# freetserv.net
KiCad netlist of a schematic drawn in EAGLE
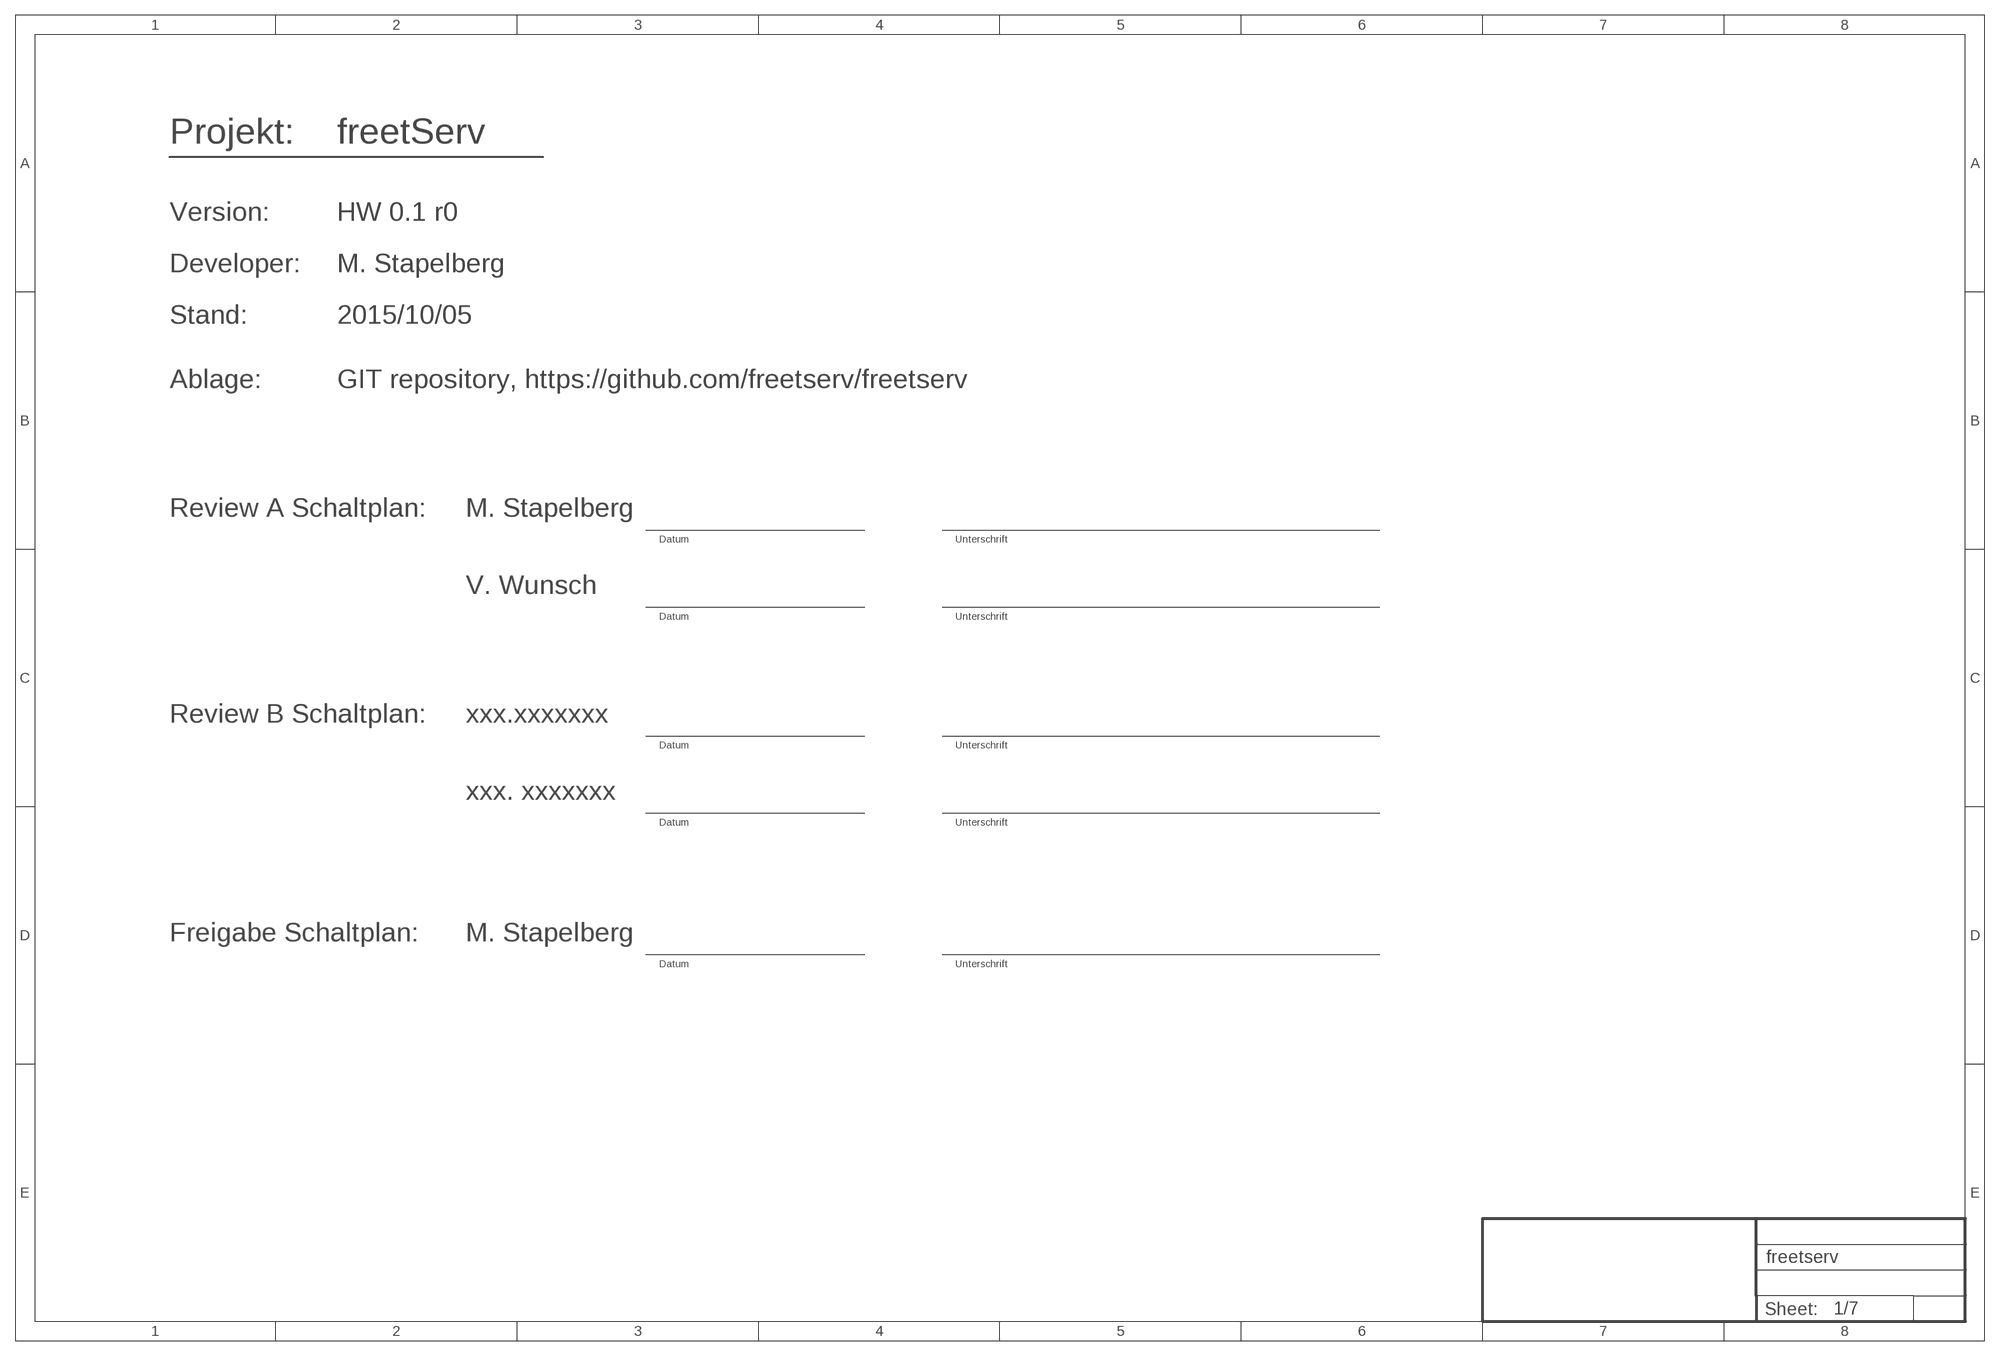
[diagram p0: schematic, sheet 1]
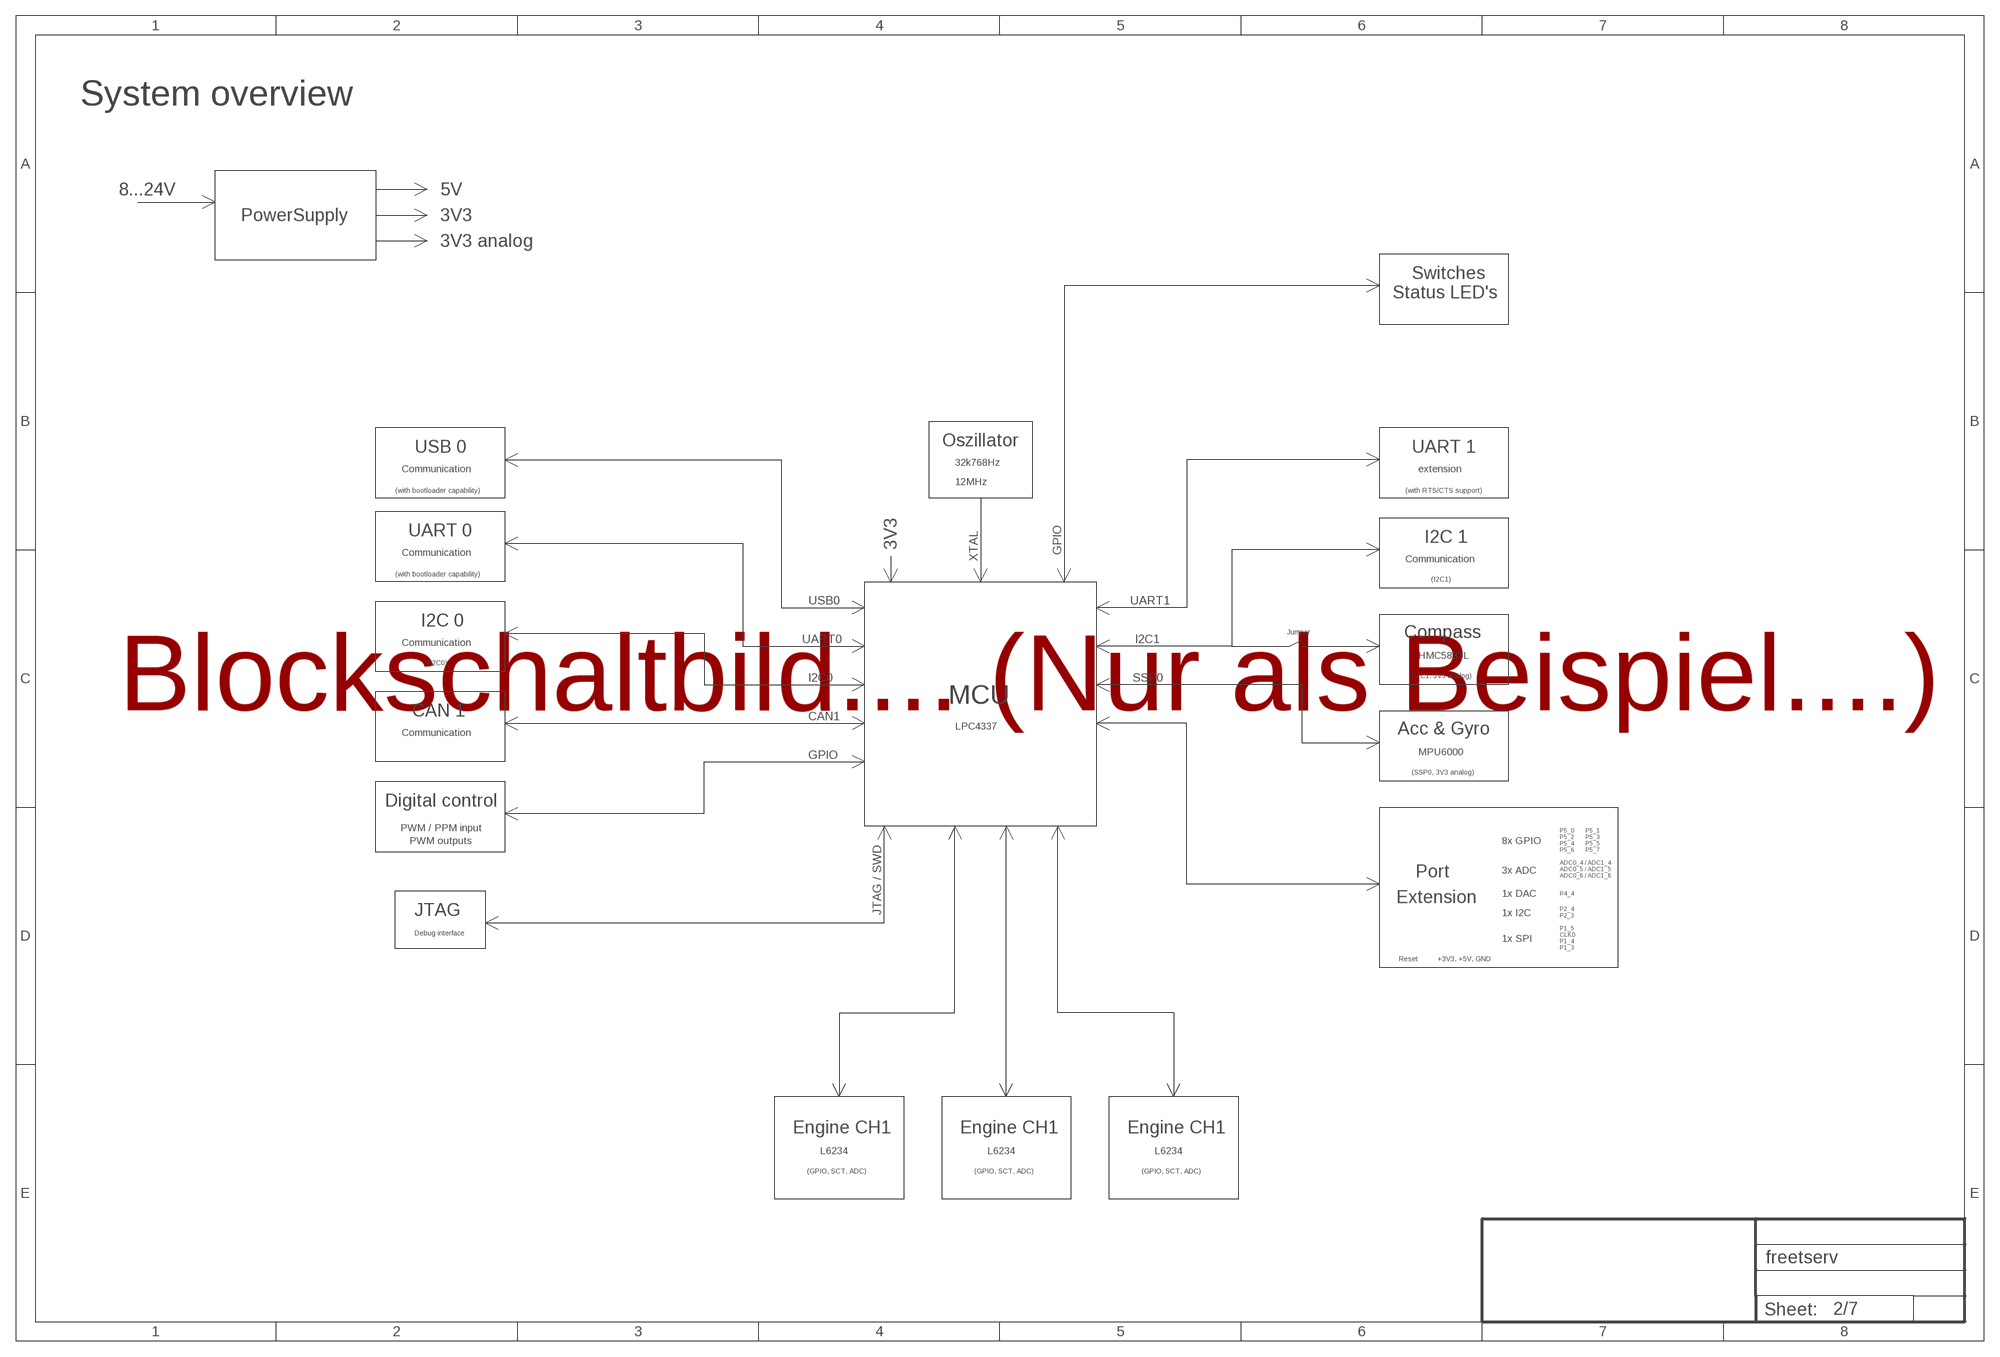
[diagram p1: schematic, sheet 2]
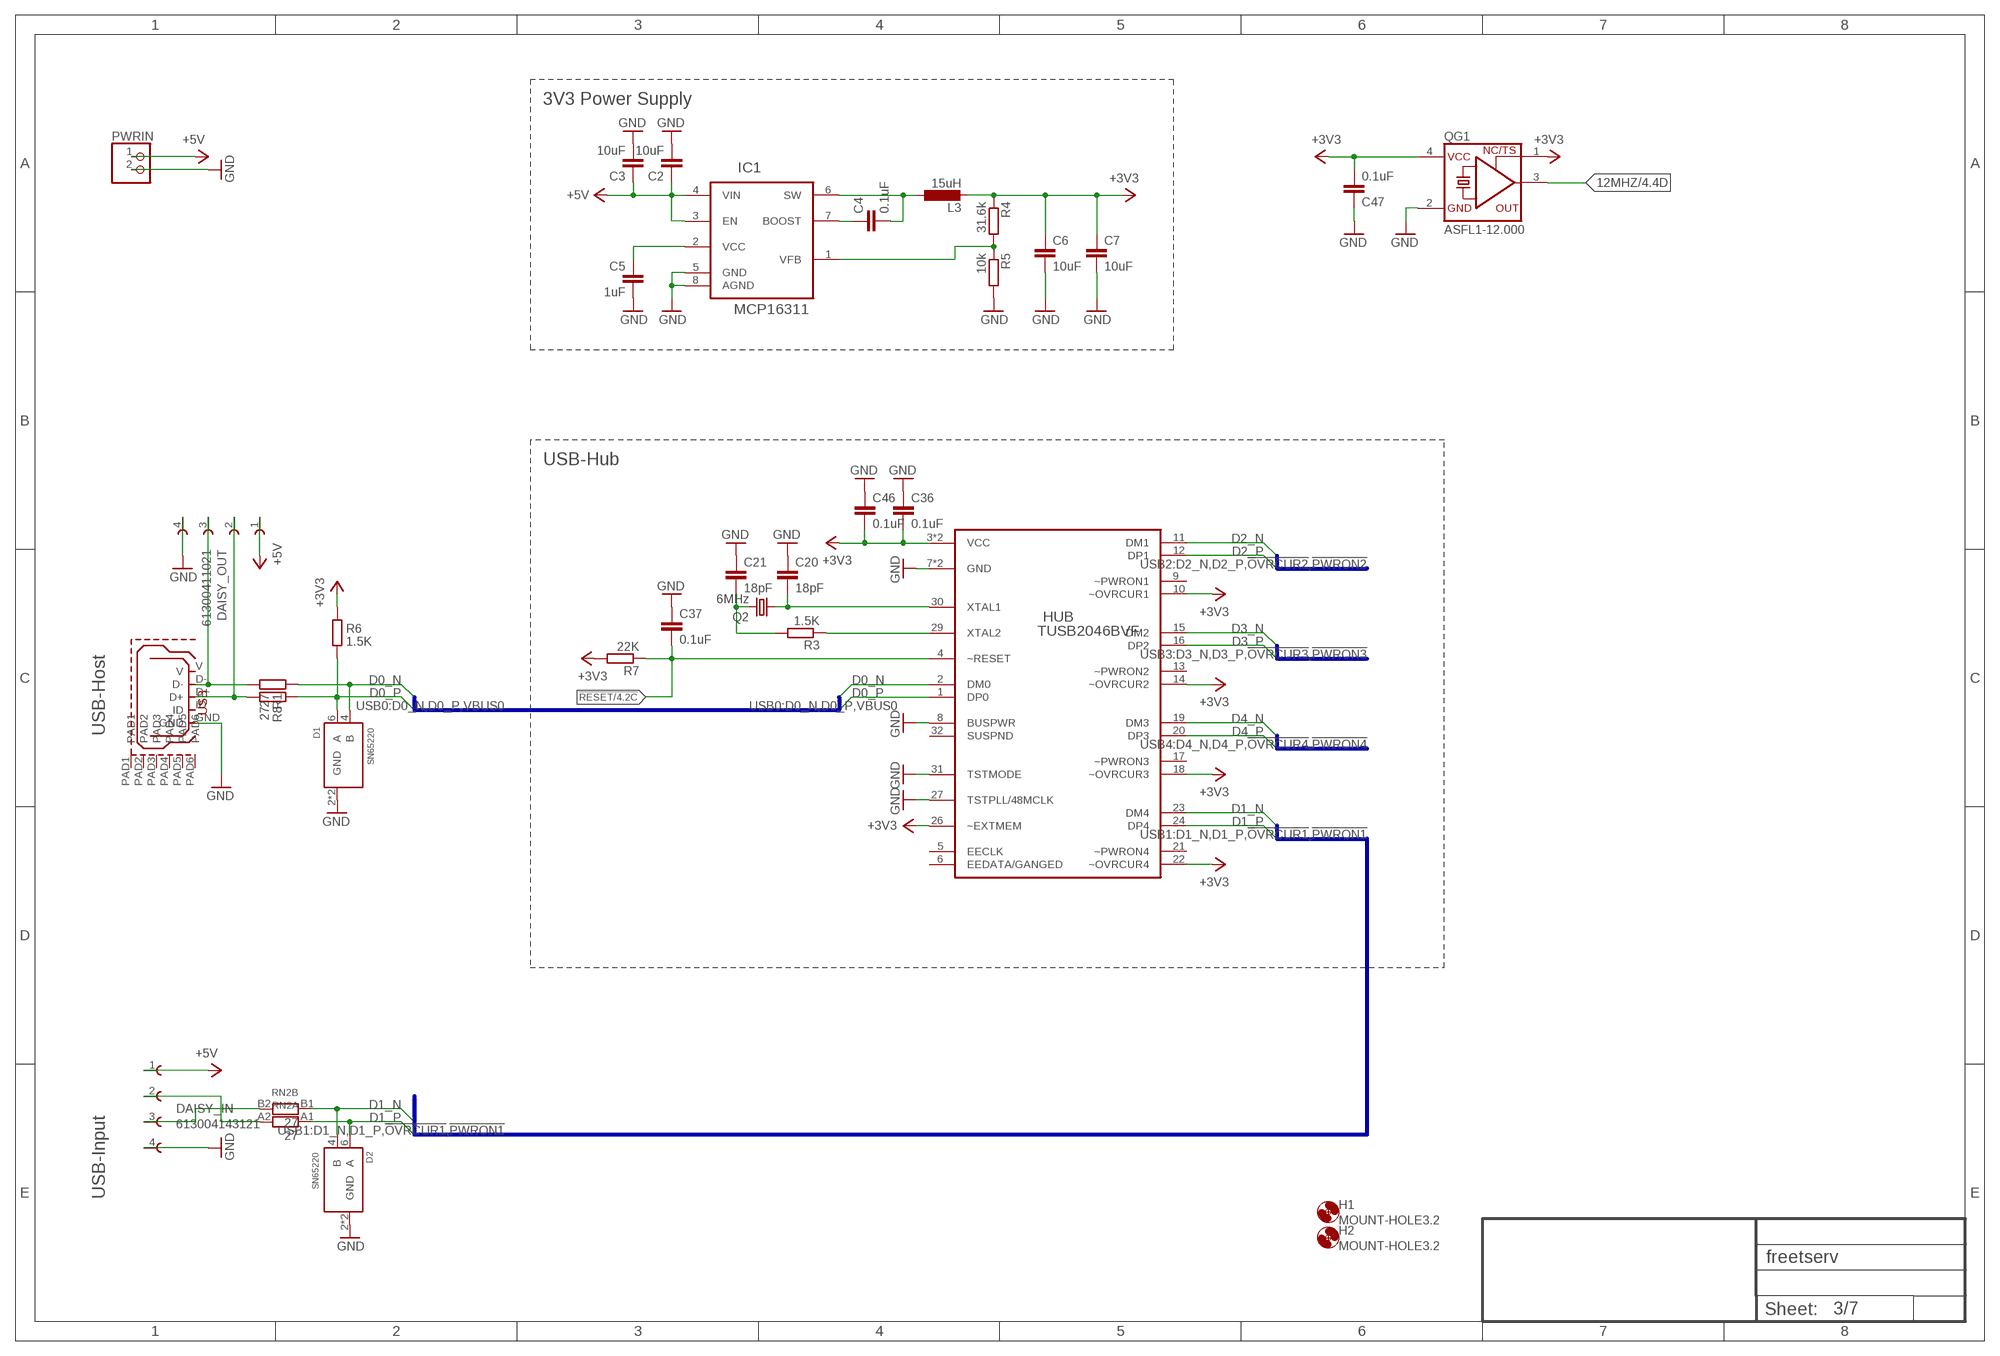
[diagram p2: schematic, sheet 3]
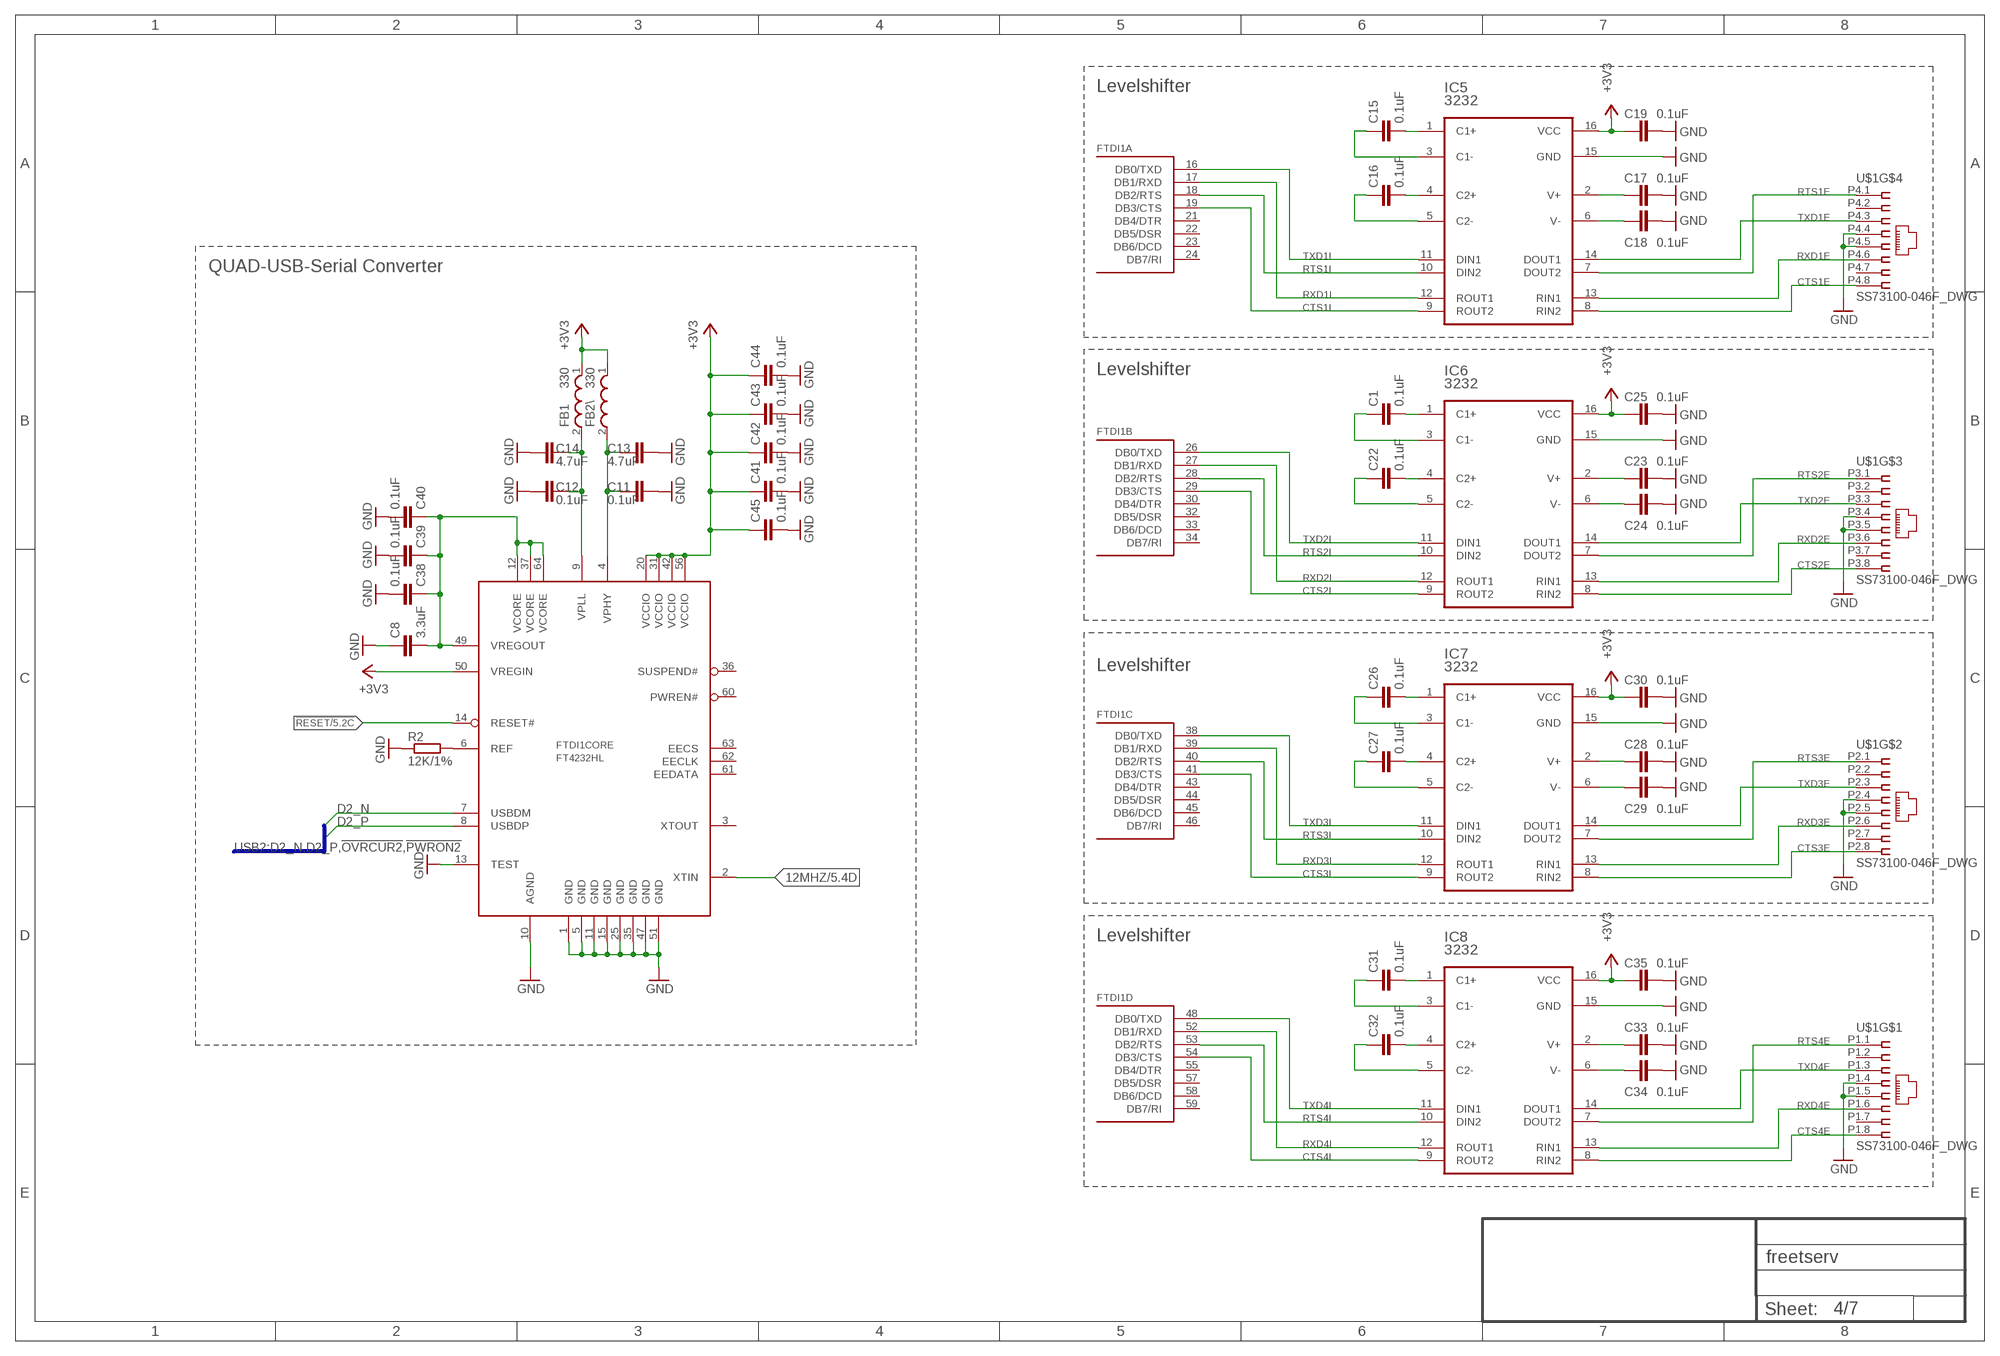
[diagram p3: schematic, sheet 4]
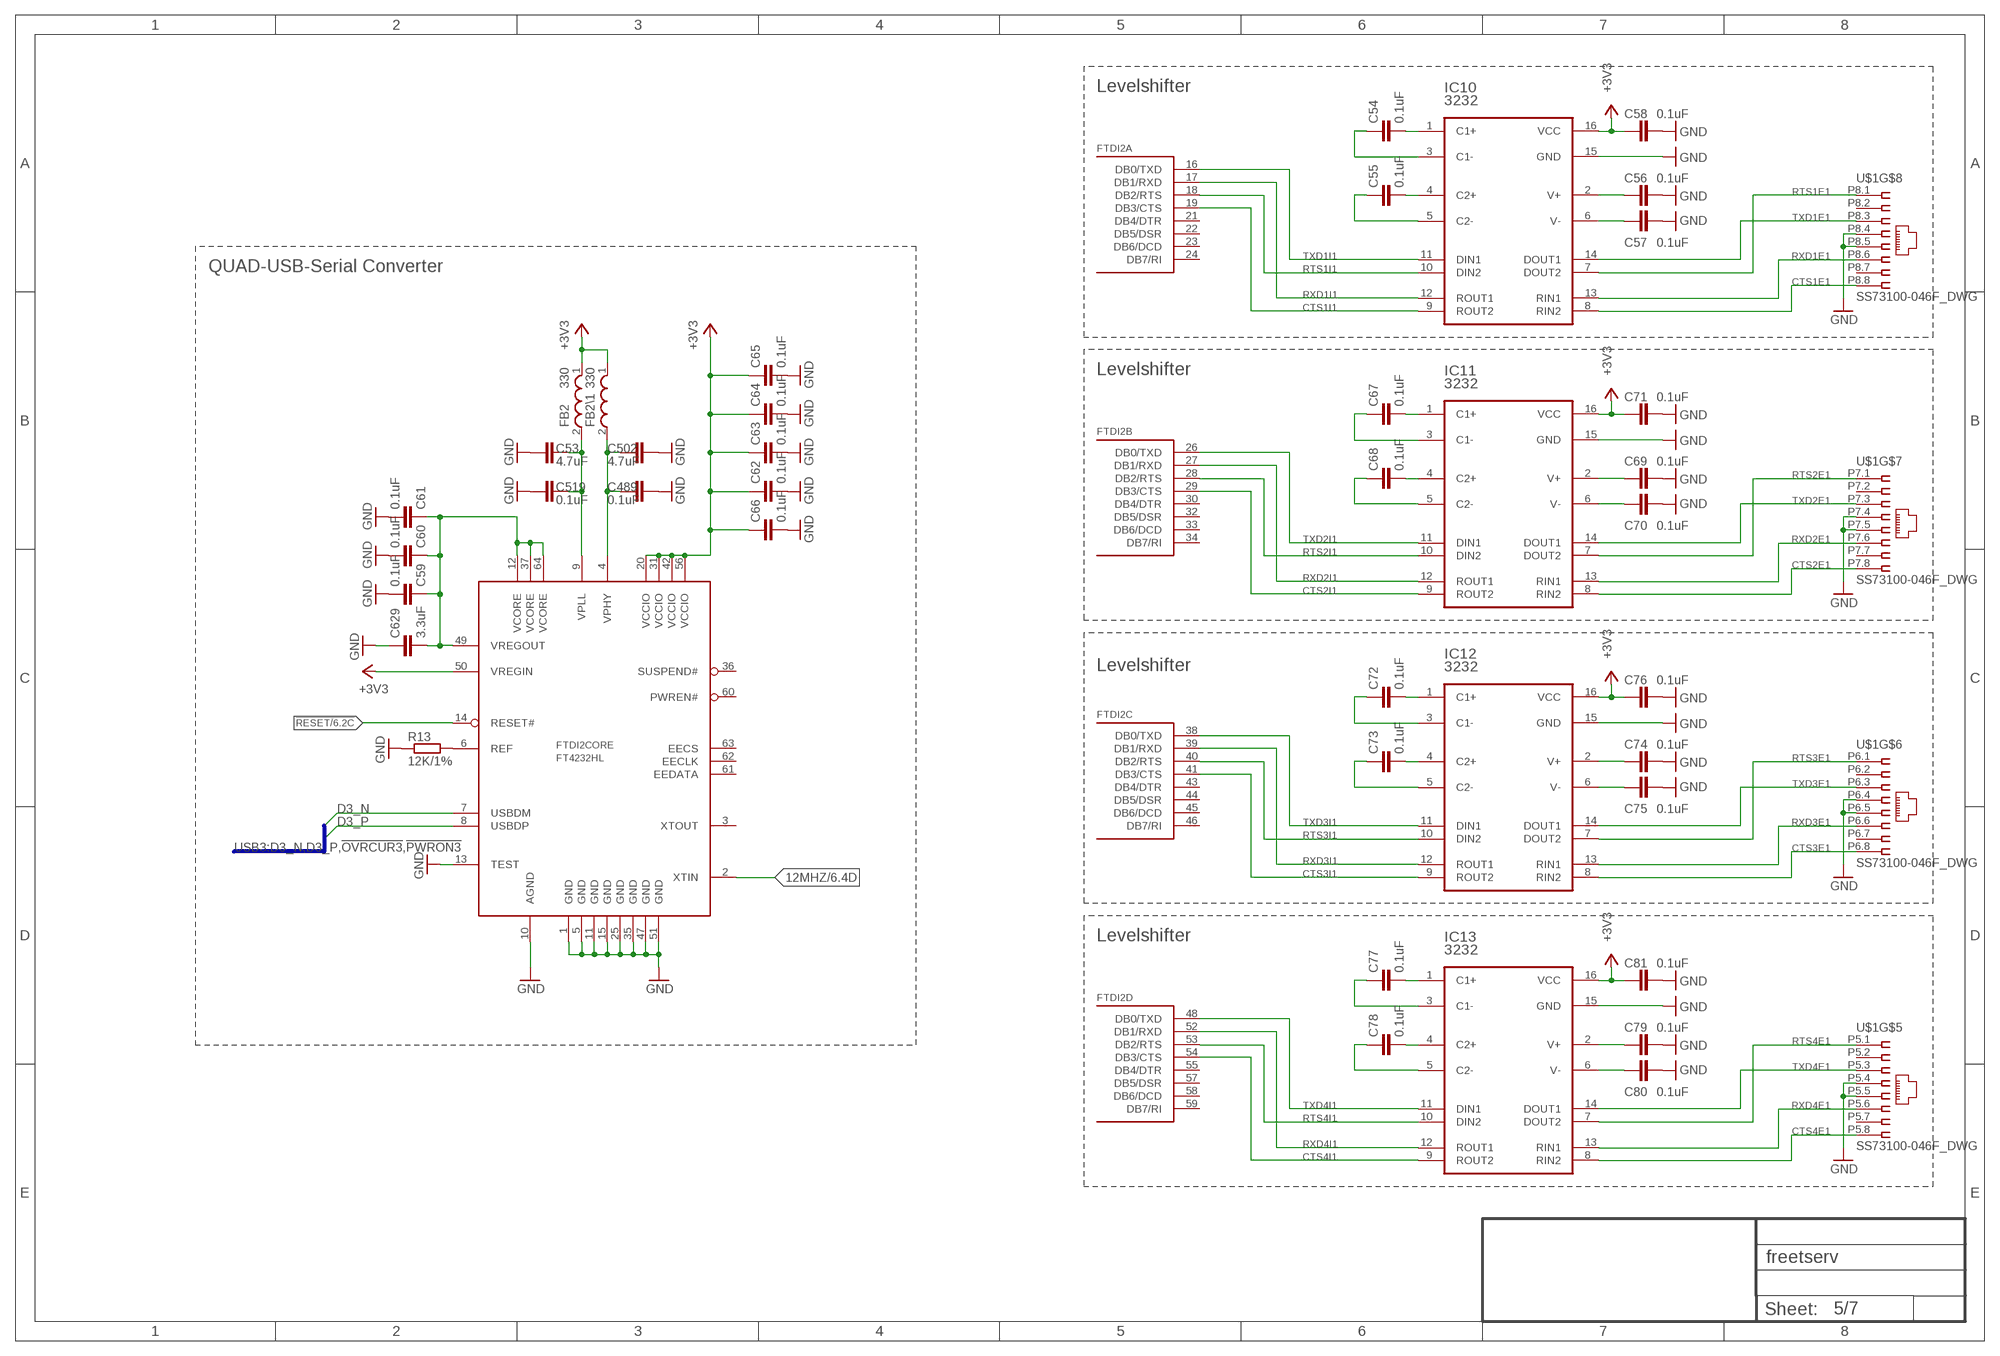
[diagram p4: schematic, sheet 5]
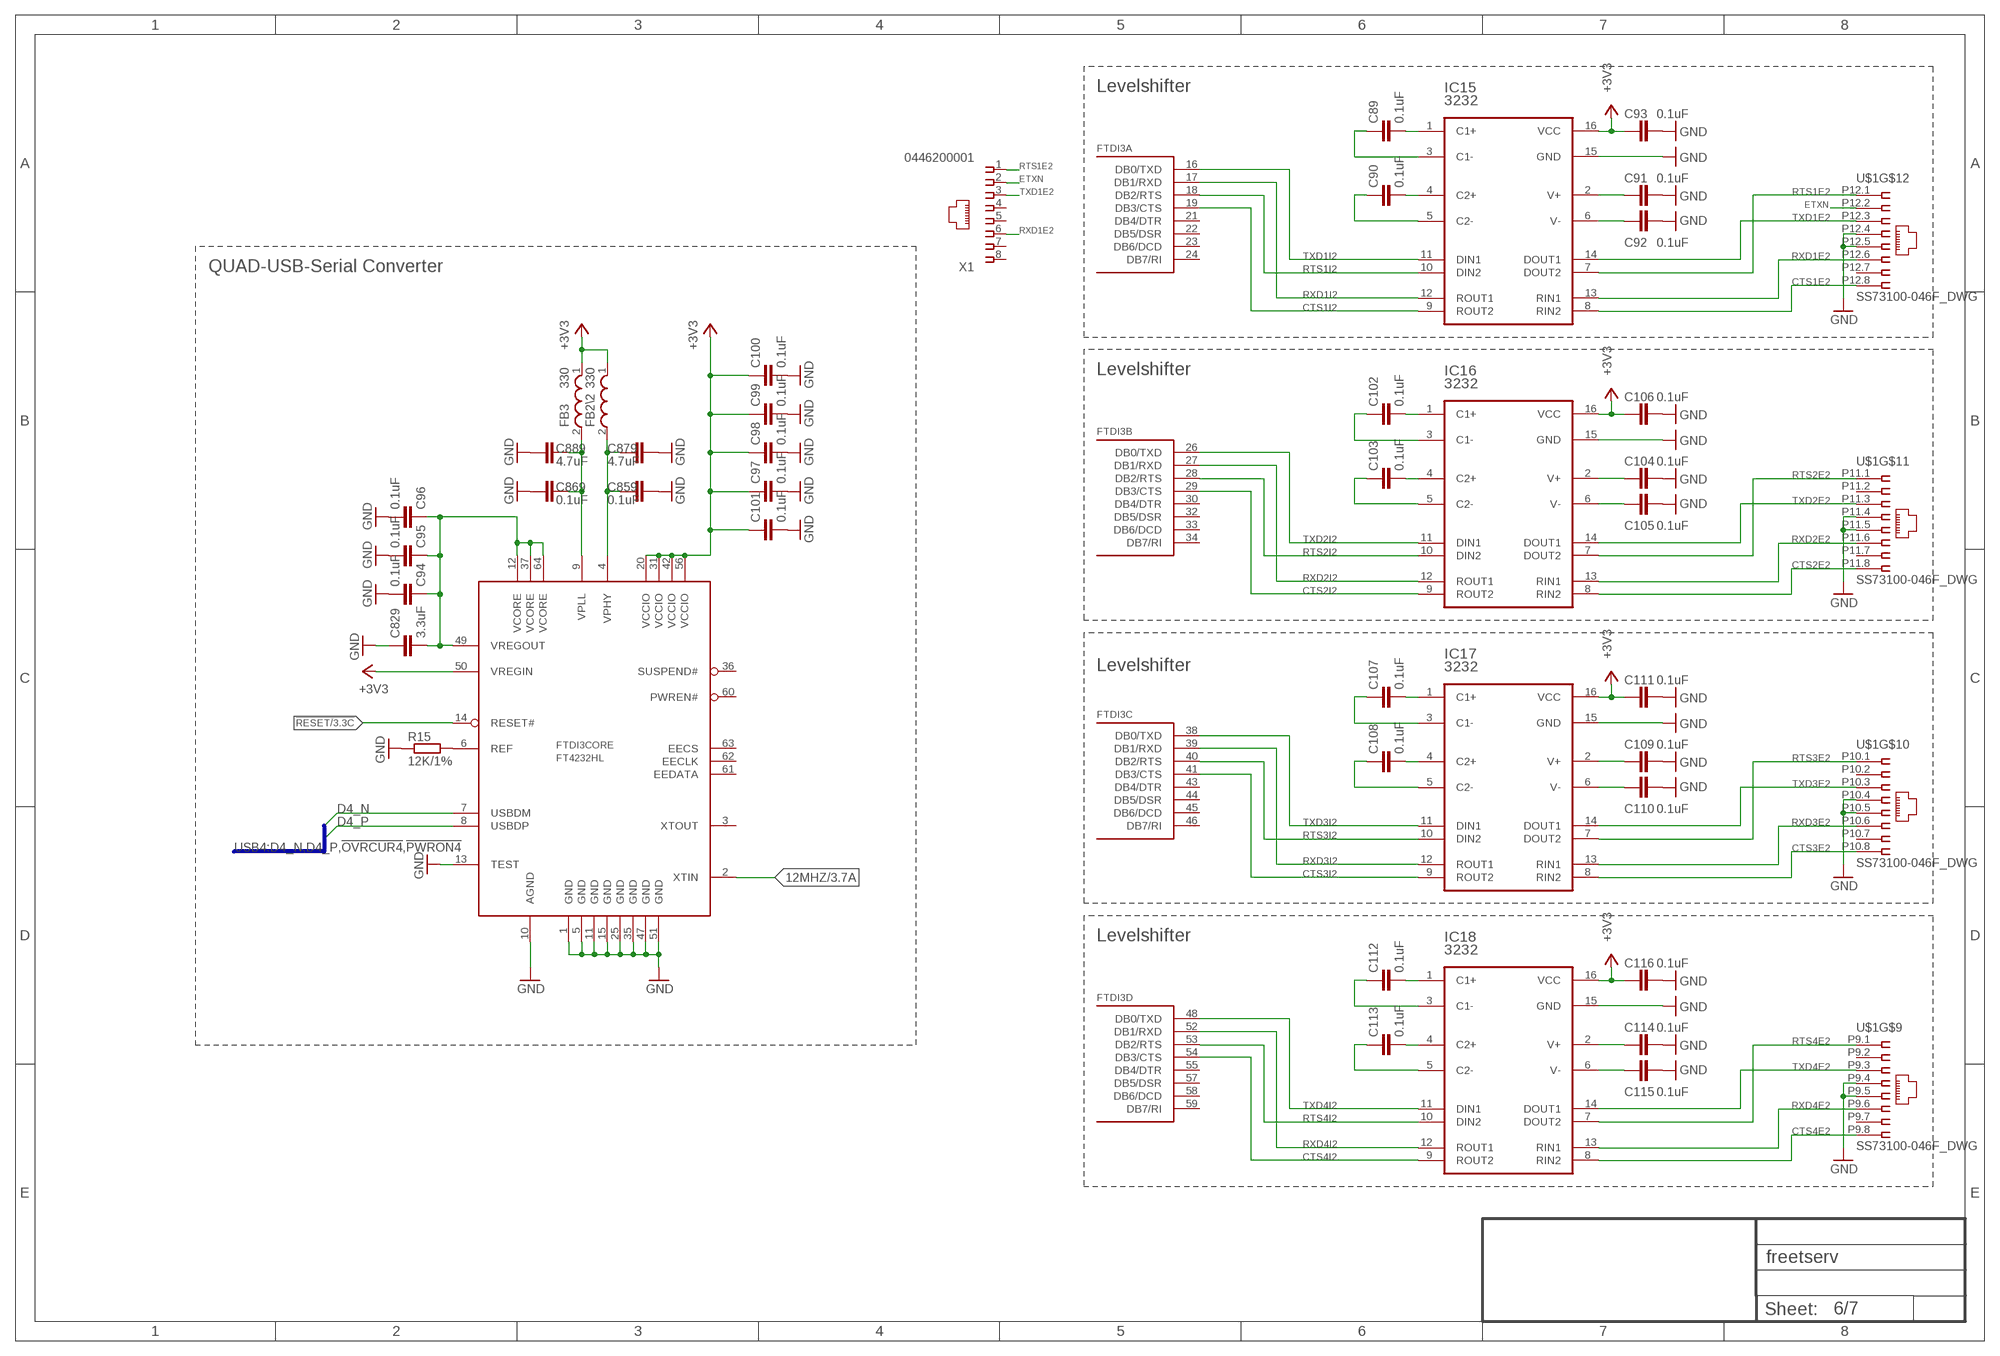
[diagram p5: schematic, sheet 6]
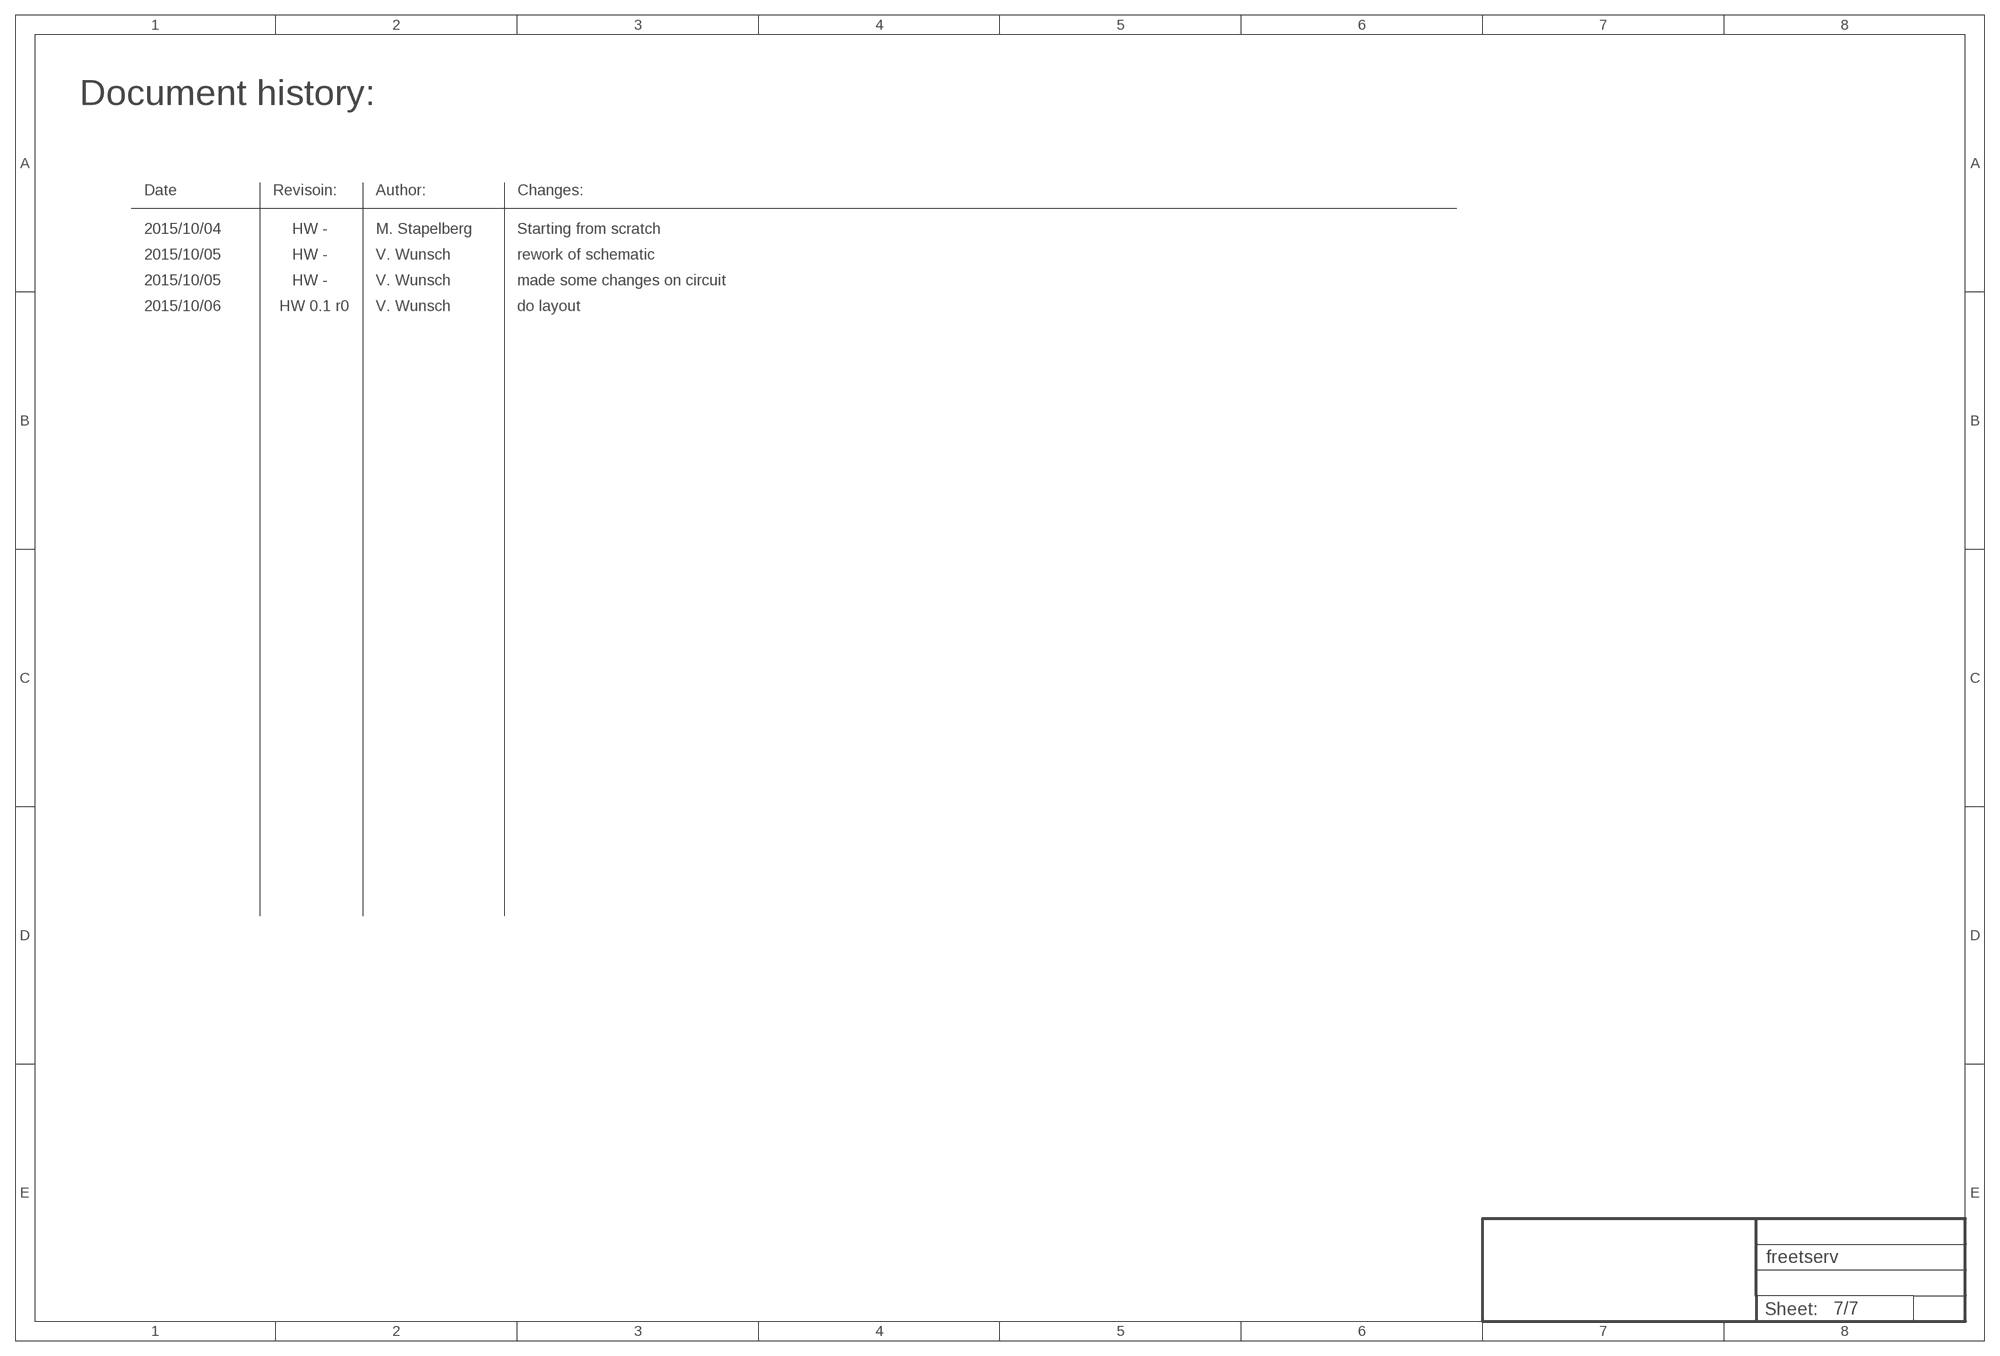
[diagram p6: schematic, sheet 7]

(export (version "E")
  (design (tool "Eeschema 10.0.6"))
  (components
    (comp (ref "C53")
      (value "4.7uF")
      (footprint "eagle-import:C0805")
      (fields (field (name "PARTNO") "1276-2972-1-ND"))
      (libsource (lib "eagle-import") (part "C-EUC0805"))
    )
    (comp (ref "C54")
      (value "0.1uF")
      (footprint "eagle-import:C0805")
      (fields (field (name "PARTNO") "1276-1003-1-ND"))
      (libsource (lib "eagle-import") (part "C-EUC0805"))
    )
    (comp (ref "C55")
      (value "0.1uF")
      (footprint "eagle-import:C0805")
      (fields (field (name "PARTNO") "1276-1003-1-ND"))
      (libsource (lib "eagle-import") (part "C-EUC0805"))
    )
    (comp (ref "C56")
      (value "0.1uF")
      (footprint "eagle-import:C0805")
      (fields (field (name "PARTNO") "1276-1003-1-ND"))
      (libsource (lib "eagle-import") (part "C-EUC0805"))
    )
    (comp (ref "C57")
      (value "0.1uF")
      (footprint "eagle-import:C0805")
      (fields (field (name "PARTNO") "1276-1003-1-ND"))
      (libsource (lib "eagle-import") (part "C-EUC0805"))
    )
    (comp (ref "C58")
      (value "0.1uF")
      (footprint "eagle-import:C0805")
      (fields (field (name "PARTNO") "1276-1003-1-ND"))
      (libsource (lib "eagle-import") (part "C-EUC0805"))
    )
    (comp (ref "C59")
      (value "0.1uF")
      (footprint "eagle-import:C0805")
      (fields (field (name "PARTNO") "1276-1003-1-ND"))
      (libsource (lib "eagle-import") (part "C-EUC0805"))
    )
    (comp (ref "C60")
      (value "0.1uF")
      (footprint "eagle-import:C0805")
      (fields (field (name "PARTNO") "1276-1003-1-ND"))
      (libsource (lib "eagle-import") (part "C-EUC0805"))
    )
    (comp (ref "C61")
      (value "0.1uF")
      (footprint "eagle-import:C0805")
      (fields (field (name "PARTNO") "1276-1003-1-ND"))
      (libsource (lib "eagle-import") (part "C-EUC0805"))
    )
    (comp (ref "C62")
      (value "0.1uF")
      (footprint "eagle-import:C0805")
      (fields (field (name "PARTNO") "1276-1003-1-ND"))
      (libsource (lib "eagle-import") (part "C-EUC0805"))
    )
    (comp (ref "C63")
      (value "0.1uF")
      (footprint "eagle-import:C0805")
      (fields (field (name "PARTNO") "1276-1003-1-ND"))
      (libsource (lib "eagle-import") (part "C-EUC0805"))
    )
    (comp (ref "C64")
      (value "0.1uF")
      (footprint "eagle-import:C0805")
      (fields (field (name "PARTNO") "1276-1003-1-ND"))
      (libsource (lib "eagle-import") (part "C-EUC0805"))
    )
    (comp (ref "C65")
      (value "0.1uF")
      (footprint "eagle-import:C0805")
      (fields (field (name "PARTNO") "1276-1003-1-ND"))
      (libsource (lib "eagle-import") (part "C-EUC0805"))
    )
    (comp (ref "C66")
      (value "0.1uF")
      (footprint "eagle-import:C0805")
      (fields (field (name "PARTNO") "1276-1003-1-ND"))
      (libsource (lib "eagle-import") (part "C-EUC0805"))
    )
    (comp (ref "C67")
      (value "0.1uF")
      (footprint "eagle-import:C0805")
      (fields (field (name "PARTNO") "1276-1003-1-ND"))
      (libsource (lib "eagle-import") (part "C-EUC0805"))
    )
    (comp (ref "C68")
      (value "0.1uF")
      (footprint "eagle-import:C0805")
      (fields (field (name "PARTNO") "1276-1003-1-ND"))
      (libsource (lib "eagle-import") (part "C-EUC0805"))
    )
    (comp (ref "C69")
      (value "0.1uF")
      (footprint "eagle-import:C0805")
      (fields (field (name "PARTNO") "1276-1003-1-ND"))
      (libsource (lib "eagle-import") (part "C-EUC0805"))
    )
    (comp (ref "C70")
      (value "0.1uF")
      (footprint "eagle-import:C0805")
      (fields (field (name "PARTNO") "1276-1003-1-ND"))
      (libsource (lib "eagle-import") (part "C-EUC0805"))
    )
    (comp (ref "C71")
      (value "0.1uF")
      (footprint "eagle-import:C0805")
      (fields (field (name "PARTNO") "1276-1003-1-ND"))
      (libsource (lib "eagle-import") (part "C-EUC0805"))
    )
    (comp (ref "C72")
      (value "0.1uF")
      (footprint "eagle-import:C0805")
      (fields (field (name "PARTNO") "1276-1003-1-ND"))
      (libsource (lib "eagle-import") (part "C-EUC0805"))
    )
    (comp (ref "C73")
      (value "0.1uF")
      (footprint "eagle-import:C0805")
      (fields (field (name "PARTNO") "1276-1003-1-ND"))
      (libsource (lib "eagle-import") (part "C-EUC0805"))
    )
    (comp (ref "C74")
      (value "0.1uF")
      (footprint "eagle-import:C0805")
      (fields (field (name "PARTNO") "1276-1003-1-ND"))
      (libsource (lib "eagle-import") (part "C-EUC0805"))
    )
    (comp (ref "C75")
      (value "0.1uF")
      (footprint "eagle-import:C0805")
      (fields (field (name "PARTNO") "1276-1003-1-ND"))
      (libsource (lib "eagle-import") (part "C-EUC0805"))
    )
    (comp (ref "C76")
      (value "0.1uF")
      (footprint "eagle-import:C0805")
      (fields (field (name "PARTNO") "1276-1003-1-ND"))
      (libsource (lib "eagle-import") (part "C-EUC0805"))
    )
    (comp (ref "C77")
      (value "0.1uF")
      (footprint "eagle-import:C0805")
      (fields (field (name "PARTNO") "1276-1003-1-ND"))
      (libsource (lib "eagle-import") (part "C-EUC0805"))
    )
    (comp (ref "C78")
      (value "0.1uF")
      (footprint "eagle-import:C0805")
      (fields (field (name "PARTNO") "1276-1003-1-ND"))
      (libsource (lib "eagle-import") (part "C-EUC0805"))
    )
    (comp (ref "C79")
      (value "0.1uF")
      (footprint "eagle-import:C0805")
      (fields (field (name "PARTNO") "1276-1003-1-ND"))
      (libsource (lib "eagle-import") (part "C-EUC0805"))
    )
    (comp (ref "C80")
      (value "0.1uF")
      (footprint "eagle-import:C0805")
      (fields (field (name "PARTNO") "1276-1003-1-ND"))
      (libsource (lib "eagle-import") (part "C-EUC0805"))
    )
    (comp (ref "C81")
      (value "0.1uF")
      (footprint "eagle-import:C0805")
      (fields (field (name "PARTNO") "1276-1003-1-ND"))
      (libsource (lib "eagle-import") (part "C-EUC0805"))
    )
    (comp (ref "C489")
      (value "0.1uF")
      (footprint "eagle-import:C0805")
      (fields (field (name "PARTNO") "1276-1003-1-ND"))
      (libsource (lib "eagle-import") (part "C-EUC0805"))
    )
    (comp (ref "C502")
      (value "4.7uF")
      (footprint "eagle-import:C0805")
      (fields (field (name "PARTNO") "1276-2972-1-ND"))
      (libsource (lib "eagle-import") (part "C-EUC0805"))
    )
    (comp (ref "C519")
      (value "0.1uF")
      (footprint "eagle-import:C0805")
      (fields (field (name "PARTNO") "1276-1003-1-ND"))
      (libsource (lib "eagle-import") (part "C-EUC0805"))
    )
    (comp (ref "C629")
      (value "3.3uF")
      (footprint "eagle-import:C0805")
      (fields (field (name "PARTNO") "445-7589-1-ND"))
      (libsource (lib "eagle-import") (part "C-EUC0805"))
    )
    (comp (ref "FB2")
      (value "330")
      (footprint "eagle-import:WE-KI_0805A")
      (fields (field (name "PARTNO") "490-5988-1-ND"))
      (libsource (lib "eagle-import") (part "WE-KI_0805A"))
    )
    (comp (ref "FB2\\1")
      (value "330")
      (footprint "eagle-import:WE-KI_0805A")
      (fields (field (name "PARTNO") "490-5988-1-ND"))
      (libsource (lib "eagle-import") (part "WE-KI_0805A"))
    )
    (comp (ref "FTDI2")
      (value "FT4232HL")
      (footprint "eagle-import:LQFP64")
      (fields (field (name "PARTNO") "768-1026-1-ND"))
      (libsource (lib "eagle-import") (part "FT4232HL"))
    )
    (comp (ref "IC10")
      (value "3232")
      (footprint "eagle-import:SOP65P640X120-16N")
      (fields (field (name "MPN") "MAX3232ECPW") (field (name "PARTNO") "296-19263-1-ND"))
      (libsource (lib "eagle-import") (part "MAX3232ECPW"))
    )
    (comp (ref "IC11")
      (value "3232")
      (footprint "eagle-import:SOP65P640X120-16N")
      (fields (field (name "MPN") "MAX3232ECPW") (field (name "PARTNO") "296-19263-1-ND"))
      (libsource (lib "eagle-import") (part "MAX3232ECPW"))
    )
    (comp (ref "IC12")
      (value "3232")
      (footprint "eagle-import:SOP65P640X120-16N")
      (fields (field (name "MPN") "MAX3232ECPW") (field (name "PARTNO") "296-19263-1-ND"))
      (libsource (lib "eagle-import") (part "MAX3232ECPW"))
    )
    (comp (ref "IC13")
      (value "3232")
      (footprint "eagle-import:SOP65P640X120-16N")
      (fields (field (name "MPN") "MAX3232ECPW") (field (name "PARTNO") "296-19263-1-ND"))
      (libsource (lib "eagle-import") (part "MAX3232ECPW"))
    )
    (comp (ref "R13")
      (value "12K/1%")
      (footprint "eagle-import:R0805")
      (fields (field (name "PARTNO") "311-12.0KCRCT-ND"))
      (libsource (lib "eagle-import") (part "R-EU_R0805"))
    )
    (comp (ref "U$1")
      (value "SS73100-046F_DWG")
      (footprint "eagle-import:SS73100-046F")
      (fields (field (name "PARTNO") "380-1225-ND"))
      (libsource (lib "eagle-import") (part "SS73100-046F_DWG"))
    )
    (comp (ref "C1")
      (value "0.1uF")
      (footprint "eagle-import:C0805")
      (fields (field (name "PARTNO") "1276-1003-1-ND"))
      (libsource (lib "eagle-import") (part "C-EUC0805"))
    )
    (comp (ref "C8")
      (value "3.3uF")
      (footprint "eagle-import:C0805")
      (fields (field (name "PARTNO") "445-7589-1-ND"))
      (libsource (lib "eagle-import") (part "C-EUC0805"))
    )
    (comp (ref "C11")
      (value "0.1uF")
      (footprint "eagle-import:C0805")
      (fields (field (name "PARTNO") "1276-1003-1-ND"))
      (libsource (lib "eagle-import") (part "C-EUC0805"))
    )
    (comp (ref "C12")
      (value "0.1uF")
      (footprint "eagle-import:C0805")
      (fields (field (name "PARTNO") "1276-1003-1-ND"))
      (libsource (lib "eagle-import") (part "C-EUC0805"))
    )
    (comp (ref "C13")
      (value "4.7uF")
      (footprint "eagle-import:C0805")
      (fields (field (name "PARTNO") "1276-2972-1-ND"))
      (libsource (lib "eagle-import") (part "C-EUC0805"))
    )
    (comp (ref "C14")
      (value "4.7uF")
      (footprint "eagle-import:C0805")
      (fields (field (name "PARTNO") "1276-2972-1-ND"))
      (libsource (lib "eagle-import") (part "C-EUC0805"))
    )
    (comp (ref "C15")
      (value "0.1uF")
      (footprint "eagle-import:C0805")
      (fields (field (name "PARTNO") "1276-1003-1-ND"))
      (libsource (lib "eagle-import") (part "C-EUC0805"))
    )
    (comp (ref "C16")
      (value "0.1uF")
      (footprint "eagle-import:C0805")
      (fields (field (name "PARTNO") "1276-1003-1-ND"))
      (libsource (lib "eagle-import") (part "C-EUC0805"))
    )
    (comp (ref "C17")
      (value "0.1uF")
      (footprint "eagle-import:C0805")
      (fields (field (name "PARTNO") "1276-1003-1-ND"))
      (libsource (lib "eagle-import") (part "C-EUC0805"))
    )
    (comp (ref "C18")
      (value "0.1uF")
      (footprint "eagle-import:C0805")
      (fields (field (name "PARTNO") "1276-1003-1-ND"))
      (libsource (lib "eagle-import") (part "C-EUC0805"))
    )
    (comp (ref "C19")
      (value "0.1uF")
      (footprint "eagle-import:C0805")
      (fields (field (name "PARTNO") "1276-1003-1-ND"))
      (libsource (lib "eagle-import") (part "C-EUC0805"))
    )
    (comp (ref "C22")
      (value "0.1uF")
      (footprint "eagle-import:C0805")
      (fields (field (name "PARTNO") "1276-1003-1-ND"))
      (libsource (lib "eagle-import") (part "C-EUC0805"))
    )
    (comp (ref "C23")
      (value "0.1uF")
      (footprint "eagle-import:C0805")
      (fields (field (name "PARTNO") "1276-1003-1-ND"))
      (libsource (lib "eagle-import") (part "C-EUC0805"))
    )
    (comp (ref "C24")
      (value "0.1uF")
      (footprint "eagle-import:C0805")
      (fields (field (name "PARTNO") "1276-1003-1-ND"))
      (libsource (lib "eagle-import") (part "C-EUC0805"))
    )
    (comp (ref "C25")
      (value "0.1uF")
      (footprint "eagle-import:C0805")
      (fields (field (name "PARTNO") "1276-1003-1-ND"))
      (libsource (lib "eagle-import") (part "C-EUC0805"))
    )
    (comp (ref "C26")
      (value "0.1uF")
      (footprint "eagle-import:C0805")
      (fields (field (name "PARTNO") "1276-1003-1-ND"))
      (libsource (lib "eagle-import") (part "C-EUC0805"))
    )
    (comp (ref "C27")
      (value "0.1uF")
      (footprint "eagle-import:C0805")
      (fields (field (name "PARTNO") "1276-1003-1-ND"))
      (libsource (lib "eagle-import") (part "C-EUC0805"))
    )
    (comp (ref "C28")
      (value "0.1uF")
      (footprint "eagle-import:C0805")
      (fields (field (name "PARTNO") "1276-1003-1-ND"))
      (libsource (lib "eagle-import") (part "C-EUC0805"))
    )
    (comp (ref "C29")
      (value "0.1uF")
      (footprint "eagle-import:C0805")
      (fields (field (name "PARTNO") "1276-1003-1-ND"))
      (libsource (lib "eagle-import") (part "C-EUC0805"))
    )
    (comp (ref "C30")
      (value "0.1uF")
      (footprint "eagle-import:C0805")
      (fields (field (name "PARTNO") "1276-1003-1-ND"))
      (libsource (lib "eagle-import") (part "C-EUC0805"))
    )
    (comp (ref "C31")
      (value "0.1uF")
      (footprint "eagle-import:C0805")
      (fields (field (name "PARTNO") "1276-1003-1-ND"))
      (libsource (lib "eagle-import") (part "C-EUC0805"))
    )
    (comp (ref "C32")
      (value "0.1uF")
      (footprint "eagle-import:C0805")
      (fields (field (name "PARTNO") "1276-1003-1-ND"))
      (libsource (lib "eagle-import") (part "C-EUC0805"))
    )
    (comp (ref "C33")
      (value "0.1uF")
      (footprint "eagle-import:C0805")
      (fields (field (name "PARTNO") "1276-1003-1-ND"))
      (libsource (lib "eagle-import") (part "C-EUC0805"))
    )
    (comp (ref "C34")
      (value "0.1uF")
      (footprint "eagle-import:C0805")
      (fields (field (name "PARTNO") "1276-1003-1-ND"))
      (libsource (lib "eagle-import") (part "C-EUC0805"))
    )
    (comp (ref "C35")
      (value "0.1uF")
      (footprint "eagle-import:C0805")
      (fields (field (name "PARTNO") "1276-1003-1-ND"))
      (libsource (lib "eagle-import") (part "C-EUC0805"))
    )
    (comp (ref "C38")
      (value "0.1uF")
      (footprint "eagle-import:C0805")
      (fields (field (name "PARTNO") "1276-1003-1-ND"))
      (libsource (lib "eagle-import") (part "C-EUC0805"))
    )
    (comp (ref "C39")
      (value "0.1uF")
      (footprint "eagle-import:C0805")
      (fields (field (name "PARTNO") "1276-1003-1-ND"))
      (libsource (lib "eagle-import") (part "C-EUC0805"))
    )
    (comp (ref "C40")
      (value "0.1uF")
      (footprint "eagle-import:C0805")
      (fields (field (name "PARTNO") "1276-1003-1-ND"))
      (libsource (lib "eagle-import") (part "C-EUC0805"))
    )
    (comp (ref "C41")
      (value "0.1uF")
      (footprint "eagle-import:C0805")
      (fields (field (name "PARTNO") "1276-1003-1-ND"))
      (libsource (lib "eagle-import") (part "C-EUC0805"))
    )
    (comp (ref "C42")
      (value "0.1uF")
      (footprint "eagle-import:C0805")
      (fields (field (name "PARTNO") "1276-1003-1-ND"))
      (libsource (lib "eagle-import") (part "C-EUC0805"))
    )
    (comp (ref "C43")
      (value "0.1uF")
      (footprint "eagle-import:C0805")
      (fields (field (name "PARTNO") "1276-1003-1-ND"))
      (libsource (lib "eagle-import") (part "C-EUC0805"))
    )
    (comp (ref "C44")
      (value "0.1uF")
      (footprint "eagle-import:C0805")
      (fields (field (name "PARTNO") "1276-1003-1-ND"))
      (libsource (lib "eagle-import") (part "C-EUC0805"))
    )
    (comp (ref "C45")
      (value "0.1uF")
      (footprint "eagle-import:C0805")
      (fields (field (name "PARTNO") "1276-1003-1-ND"))
      (libsource (lib "eagle-import") (part "C-EUC0805"))
    )
    (comp (ref "FB1")
      (value "330")
      (footprint "eagle-import:WE-KI_0805A")
      (fields (field (name "PARTNO") "490-5988-1-ND"))
      (libsource (lib "eagle-import") (part "WE-KI_0805A"))
    )
    (comp (ref "FB2\\")
      (value "330")
      (footprint "eagle-import:WE-KI_0805A")
      (fields (field (name "PARTNO") "490-5988-1-ND"))
      (libsource (lib "eagle-import") (part "WE-KI_0805A"))
    )
    (comp (ref "FTDI1")
      (value "FT4232HL")
      (footprint "eagle-import:LQFP64")
      (fields (field (name "PARTNO") "768-1026-1-ND"))
      (libsource (lib "eagle-import") (part "FT4232HL"))
    )
    (comp (ref "IC5")
      (value "3232")
      (footprint "eagle-import:SOP65P640X120-16N")
      (fields (field (name "MPN") "MAX3232ECPW") (field (name "PARTNO") "296-19263-1-ND"))
      (libsource (lib "eagle-import") (part "MAX3232ECPW"))
    )
    (comp (ref "IC6")
      (value "3232")
      (footprint "eagle-import:SOP65P640X120-16N")
      (fields (field (name "MPN") "MAX3232ECPW") (field (name "PARTNO") "296-19263-1-ND"))
      (libsource (lib "eagle-import") (part "MAX3232ECPW"))
    )
    (comp (ref "IC7")
      (value "3232")
      (footprint "eagle-import:SOP65P640X120-16N")
      (fields (field (name "MPN") "MAX3232ECPW") (field (name "PARTNO") "296-19263-1-ND"))
      (libsource (lib "eagle-import") (part "MAX3232ECPW"))
    )
    (comp (ref "IC8")
      (value "3232")
      (footprint "eagle-import:SOP65P640X120-16N")
      (fields (field (name "MPN") "MAX3232ECPW") (field (name "PARTNO") "296-19263-1-ND"))
      (libsource (lib "eagle-import") (part "MAX3232ECPW"))
    )
    (comp (ref "R2")
      (value "12K/1%")
      (footprint "eagle-import:R0805")
      (fields (field (name "PARTNO") "311-12.0KCRCT-ND"))
      (libsource (lib "eagle-import") (part "R-EU_R0805"))
    )
    (comp (ref "C89")
      (value "0.1uF")
      (footprint "eagle-import:C0805")
      (fields (field (name "PARTNO") "1276-1003-1-ND"))
      (libsource (lib "eagle-import") (part "C-EUC0805"))
    )
    (comp (ref "C90")
      (value "0.1uF")
      (footprint "eagle-import:C0805")
      (fields (field (name "PARTNO") "1276-1003-1-ND"))
      (libsource (lib "eagle-import") (part "C-EUC0805"))
    )
    (comp (ref "C91")
      (value "0.1uF")
      (footprint "eagle-import:C0805")
      (fields (field (name "PARTNO") "1276-1003-1-ND"))
      (libsource (lib "eagle-import") (part "C-EUC0805"))
    )
    (comp (ref "C92")
      (value "0.1uF")
      (footprint "eagle-import:C0805")
      (fields (field (name "PARTNO") "1276-1003-1-ND"))
      (libsource (lib "eagle-import") (part "C-EUC0805"))
    )
    (comp (ref "C93")
      (value "0.1uF")
      (footprint "eagle-import:C0805")
      (fields (field (name "PARTNO") "1276-1003-1-ND"))
      (libsource (lib "eagle-import") (part "C-EUC0805"))
    )
    (comp (ref "C94")
      (value "0.1uF")
      (footprint "eagle-import:C0805")
      (fields (field (name "PARTNO") "1276-1003-1-ND"))
      (libsource (lib "eagle-import") (part "C-EUC0805"))
    )
    (comp (ref "C95")
      (value "0.1uF")
      (footprint "eagle-import:C0805")
      (fields (field (name "PARTNO") "1276-1003-1-ND"))
      (libsource (lib "eagle-import") (part "C-EUC0805"))
    )
    (comp (ref "C96")
      (value "0.1uF")
      (footprint "eagle-import:C0805")
      (fields (field (name "PARTNO") "1276-1003-1-ND"))
      (libsource (lib "eagle-import") (part "C-EUC0805"))
    )
    (comp (ref "C97")
      (value "0.1uF")
      (footprint "eagle-import:C0805")
      (fields (field (name "PARTNO") "1276-1003-1-ND"))
      (libsource (lib "eagle-import") (part "C-EUC0805"))
    )
    (comp (ref "C98")
      (value "0.1uF")
      (footprint "eagle-import:C0805")
      (fields (field (name "PARTNO") "1276-1003-1-ND"))
      (libsource (lib "eagle-import") (part "C-EUC0805"))
    )
    (comp (ref "C99")
      (value "0.1uF")
      (footprint "eagle-import:C0805")
      (fields (field (name "PARTNO") "1276-1003-1-ND"))
      (libsource (lib "eagle-import") (part "C-EUC0805"))
    )
    (comp (ref "C100")
      (value "0.1uF")
      (footprint "eagle-import:C0805")
      (fields (field (name "PARTNO") "1276-1003-1-ND"))
      (libsource (lib "eagle-import") (part "C-EUC0805"))
    )
    (comp (ref "C101")
      (value "0.1uF")
      (footprint "eagle-import:C0805")
      (fields (field (name "PARTNO") "1276-1003-1-ND"))
      (libsource (lib "eagle-import") (part "C-EUC0805"))
    )
    (comp (ref "C102")
      (value "0.1uF")
      (footprint "eagle-import:C0805")
      (fields (field (name "PARTNO") "1276-1003-1-ND"))
      (libsource (lib "eagle-import") (part "C-EUC0805"))
    )
    (comp (ref "C103")
      (value "0.1uF")
      (footprint "eagle-import:C0805")
      (fields (field (name "PARTNO") "1276-1003-1-ND"))
      (libsource (lib "eagle-import") (part "C-EUC0805"))
    )
    (comp (ref "C104")
      (value "0.1uF")
      (footprint "eagle-import:C0805")
      (fields (field (name "PARTNO") "1276-1003-1-ND"))
      (libsource (lib "eagle-import") (part "C-EUC0805"))
    )
    (comp (ref "C105")
      (value "0.1uF")
      (footprint "eagle-import:C0805")
      (fields (field (name "PARTNO") "1276-1003-1-ND"))
      (libsource (lib "eagle-import") (part "C-EUC0805"))
    )
    (comp (ref "C106")
      (value "0.1uF")
      (footprint "eagle-import:C0805")
      (fields (field (name "PARTNO") "1276-1003-1-ND"))
      (libsource (lib "eagle-import") (part "C-EUC0805"))
    )
    (comp (ref "C107")
      (value "0.1uF")
      (footprint "eagle-import:C0805")
      (fields (field (name "PARTNO") "1276-1003-1-ND"))
      (libsource (lib "eagle-import") (part "C-EUC0805"))
    )
    (comp (ref "C108")
      (value "0.1uF")
      (footprint "eagle-import:C0805")
      (fields (field (name "PARTNO") "1276-1003-1-ND"))
      (libsource (lib "eagle-import") (part "C-EUC0805"))
    )
    (comp (ref "C109")
      (value "0.1uF")
      (footprint "eagle-import:C0805")
      (fields (field (name "PARTNO") "1276-1003-1-ND"))
      (libsource (lib "eagle-import") (part "C-EUC0805"))
    )
    (comp (ref "C110")
      (value "0.1uF")
      (footprint "eagle-import:C0805")
      (fields (field (name "PARTNO") "1276-1003-1-ND"))
      (libsource (lib "eagle-import") (part "C-EUC0805"))
    )
    (comp (ref "C111")
      (value "0.1uF")
      (footprint "eagle-import:C0805")
      (fields (field (name "PARTNO") "1276-1003-1-ND"))
      (libsource (lib "eagle-import") (part "C-EUC0805"))
    )
    (comp (ref "C112")
      (value "0.1uF")
      (footprint "eagle-import:C0805")
      (fields (field (name "PARTNO") "1276-1003-1-ND"))
      (libsource (lib "eagle-import") (part "C-EUC0805"))
    )
    (comp (ref "C113")
      (value "0.1uF")
      (footprint "eagle-import:C0805")
      (fields (field (name "PARTNO") "1276-1003-1-ND"))
      (libsource (lib "eagle-import") (part "C-EUC0805"))
    )
    (comp (ref "C114")
      (value "0.1uF")
      (footprint "eagle-import:C0805")
      (fields (field (name "PARTNO") "1276-1003-1-ND"))
      (libsource (lib "eagle-import") (part "C-EUC0805"))
    )
    (comp (ref "C115")
      (value "0.1uF")
      (footprint "eagle-import:C0805")
      (fields (field (name "PARTNO") "1276-1003-1-ND"))
      (libsource (lib "eagle-import") (part "C-EUC0805"))
    )
    (comp (ref "C116")
      (value "0.1uF")
      (footprint "eagle-import:C0805")
      (fields (field (name "PARTNO") "1276-1003-1-ND"))
      (libsource (lib "eagle-import") (part "C-EUC0805"))
    )
    (comp (ref "C829")
      (value "3.3uF")
      (footprint "eagle-import:C0805")
      (fields (field (name "PARTNO") "445-7589-1-ND"))
      (libsource (lib "eagle-import") (part "C-EUC0805"))
    )
    (comp (ref "C859")
      (value "0.1uF")
      (footprint "eagle-import:C0805")
      (fields (field (name "PARTNO") "1276-1003-1-ND"))
      (libsource (lib "eagle-import") (part "C-EUC0805"))
    )
    (comp (ref "C869")
      (value "0.1uF")
      (footprint "eagle-import:C0805")
      (fields (field (name "PARTNO") "1276-1003-1-ND"))
      (libsource (lib "eagle-import") (part "C-EUC0805"))
    )
    (comp (ref "C879")
      (value "4.7uF")
      (footprint "eagle-import:C0805")
      (fields (field (name "PARTNO") "1276-2972-1-ND"))
      (libsource (lib "eagle-import") (part "C-EUC0805"))
    )
    (comp (ref "C889")
      (value "4.7uF")
      (footprint "eagle-import:C0805")
      (fields (field (name "PARTNO") "1276-2972-1-ND"))
      (libsource (lib "eagle-import") (part "C-EUC0805"))
    )
    (comp (ref "FB2\\2")
      (value "330")
      (footprint "eagle-import:WE-KI_0805A")
      (fields (field (name "PARTNO") "490-5988-1-ND"))
      (libsource (lib "eagle-import") (part "WE-KI_0805A"))
    )
    (comp (ref "FB3")
      (value "330")
      (footprint "eagle-import:WE-KI_0805A")
      (fields (field (name "PARTNO") "490-5988-1-ND"))
      (libsource (lib "eagle-import") (part "WE-KI_0805A"))
    )
    (comp (ref "FTDI3")
      (value "FT4232HL")
      (footprint "eagle-import:LQFP64")
      (fields (field (name "PARTNO") "768-1026-1-ND"))
      (libsource (lib "eagle-import") (part "FT4232HL"))
    )
    (comp (ref "IC15")
      (value "3232")
      (footprint "eagle-import:SOP65P640X120-16N")
      (fields (field (name "MPN") "MAX3232ECPW") (field (name "PARTNO") "296-19263-1-ND"))
      (libsource (lib "eagle-import") (part "MAX3232ECPW"))
    )
    (comp (ref "IC16")
      (value "3232")
      (footprint "eagle-import:SOP65P640X120-16N")
      (fields (field (name "MPN") "MAX3232ECPW") (field (name "PARTNO") "296-19263-1-ND"))
      (libsource (lib "eagle-import") (part "MAX3232ECPW"))
    )
    (comp (ref "IC17")
      (value "3232")
      (footprint "eagle-import:SOP65P640X120-16N")
      (fields (field (name "MPN") "MAX3232ECPW") (field (name "PARTNO") "296-19263-1-ND"))
      (libsource (lib "eagle-import") (part "MAX3232ECPW"))
    )
    (comp (ref "IC18")
      (value "3232")
      (footprint "eagle-import:SOP65P640X120-16N")
      (fields (field (name "MPN") "MAX3232ECPW") (field (name "PARTNO") "296-19263-1-ND"))
      (libsource (lib "eagle-import") (part "MAX3232ECPW"))
    )
    (comp (ref "R15")
      (value "12K/1%")
      (footprint "eagle-import:R0805")
      (fields (field (name "PARTNO") "311-12.0KCRCT-ND"))
      (libsource (lib "eagle-import") (part "R-EU_R0805"))
    )
    (comp (ref "X1")
      (value "0446200001")
      (footprint "eagle-import:0446200001")
      (libsource (lib "eagle-import") (part "0446200001"))
    )
    (comp (ref "C2")
      (value "10uF")
      (footprint "eagle-import:C0805")
      (fields (field (name "PARTNO") "490-10517-1-ND"))
      (libsource (lib "eagle-import") (part "C-EUC0805"))
    )
    (comp (ref "C3")
      (value "10uF")
      (footprint "eagle-import:C0805")
      (fields (field (name "PARTNO") "490-10517-1-ND"))
      (libsource (lib "eagle-import") (part "C-EUC0805"))
    )
    (comp (ref "C4")
      (value "0.1uF")
      (footprint "eagle-import:C0805")
      (fields (field (name "PARTNO") "1276-1003-1-ND"))
      (libsource (lib "eagle-import") (part "C-EUC0805"))
    )
    (comp (ref "C5")
      (value "1uF")
      (footprint "eagle-import:C0805")
      (fields (field (name "PARTNO") "311-1365-1-ND"))
      (libsource (lib "eagle-import") (part "C-EUC0805"))
    )
    (comp (ref "C6")
      (value "10uF")
      (footprint "eagle-import:C0805")
      (fields (field (name "PARTNO") "490-10517-1-ND"))
      (libsource (lib "eagle-import") (part "C-EUC0805"))
    )
    (comp (ref "C7")
      (value "10uF")
      (footprint "eagle-import:C0805")
      (fields (field (name "PARTNO") "490-10517-1-ND"))
      (libsource (lib "eagle-import") (part "C-EUC0805"))
    )
    (comp (ref "C20")
      (value "18pF")
      (footprint "eagle-import:C0805")
      (fields (field (name "PARTNO") "709-1171-1-ND"))
      (libsource (lib "eagle-import") (part "C-EUC0805"))
    )
    (comp (ref "C21")
      (value "18pF")
      (footprint "eagle-import:C0805")
      (fields (field (name "PARTNO") "709-1171-1-ND"))
      (libsource (lib "eagle-import") (part "C-EUC0805"))
    )
    (comp (ref "C36")
      (value "0.1uF")
      (footprint "eagle-import:C0805")
      (fields (field (name "PARTNO") "1276-1003-1-ND"))
      (libsource (lib "eagle-import") (part "C-EUC0805"))
    )
    (comp (ref "C37")
      (value "0.1uF")
      (footprint "eagle-import:C0805")
      (fields (field (name "PARTNO") "1276-1003-1-ND"))
      (libsource (lib "eagle-import") (part "C-EUC0805"))
    )
    (comp (ref "C46")
      (value "0.1uF")
      (footprint "eagle-import:C0805")
      (fields (field (name "PARTNO") "1276-1003-1-ND"))
      (libsource (lib "eagle-import") (part "C-EUC0805"))
    )
    (comp (ref "C47")
      (value "0.1uF")
      (footprint "eagle-import:C0805")
      (fields (field (name "PARTNO") "1276-1003-1-ND"))
      (libsource (lib "eagle-import") (part "C-EUC0805"))
    )
    (comp (ref "D1")
      (value "SN65220")
      (footprint "eagle-import:SOT23-6")
      (fields (field (name "PARTNO") "296-9694-1-ND"))
      (libsource (lib "eagle-import") (part "SN65220"))
    )
    (comp (ref "D2")
      (value "SN65220")
      (footprint "eagle-import:SOT23-6")
      (fields (field (name "PARTNO") "296-9694-1-ND"))
      (libsource (lib "eagle-import") (part "SN65220"))
    )
    (comp (ref "DAISY_IN")
      (value "613004143121")
      (footprint "eagle-import:613004143121")
      (fields (field (name "PARTNO") "732-2863-ND"))
      (libsource (lib "eagle-import") (part "613004143121"))
    )
    (comp (ref "DAISY_OUT")
      (value "61300411021")
      (footprint "eagle-import:61300411021")
      (fields (field (name "PARTNO") "732-5337-ND"))
      (libsource (lib "eagle-import") (part "61300411021"))
    )
    (comp (ref "H1")
      (value "MOUNT-HOLE3.2")
      (footprint "eagle-import:3,2")
      (libsource (lib "eagle-import") (part "MOUNT-HOLE3.2"))
    )
    (comp (ref "H2")
      (value "MOUNT-HOLE3.2")
      (footprint "eagle-import:3,2")
      (libsource (lib "eagle-import") (part "MOUNT-HOLE3.2"))
    )
    (comp (ref "HUB")
      (value "TUSB2046BVF")
      (footprint "eagle-import:QFP80P900X900X145-32N")
      (libsource (lib "eagle-import") (part "TUSB2046BVF"))
    )
    (comp (ref "IC1")
      (value "MCP16311")
      (footprint "eagle-import:MSOP8")
      (fields (field (name "PARTNO") "MCP16311-E/MS-ND"))
      (libsource (lib "eagle-import") (part "MCP16311-E/MS"))
    )
    (comp (ref "L3")
      (value "15uH")
      (footprint "eagle-import:NR60XX")
      (fields (field (name "PARTNO") "587-2624-1-ND"))
      (libsource (lib "eagle-import") (part "NR6028T220M"))
    )
    (comp (ref "PWRIN")
      (value "PINHD-1X2")
      (footprint "eagle-import:1X02")
      (fields (field (name "PARTNO") "A1921-ND"))
      (libsource (lib "eagle-import") (part "PINHD-1X2"))
    )
    (comp (ref "Q2")
      (value "6MHz")
      (footprint "eagle-import:CSM-7X-DU")
      (fields (field (name "PARTNO") "535-10208-1-ND"))
      (libsource (lib "eagle-import") (part "CSM-7X-DU"))
    )
    (comp (ref "QG1")
      (value "ASFL1-12.000")
      (footprint "eagle-import:XO53")
      (fields (field (name "PARTNO") "535-9253-1-ND"))
      (libsource (lib "eagle-import") (part "XO-XO53"))
    )
    (comp (ref "R1")
      (value "27")
      (footprint "eagle-import:R0805")
      (fields (field (name "PARTNO") "311-27ARCT-ND"))
      (libsource (lib "eagle-import") (part "R-EU_R0805"))
    )
    (comp (ref "R3")
      (value "1.5K")
      (footprint "eagle-import:R0805")
      (fields (field (name "PARTNO") "311-1.5KARCT-ND"))
      (libsource (lib "eagle-import") (part "R-EU_R0805"))
    )
    (comp (ref "R4")
      (value "31.6k")
      (footprint "eagle-import:R0805")
      (fields (field (name "PARTNO") "311-31.6KCRCT-ND"))
      (libsource (lib "eagle-import") (part "R-EU_R0805"))
    )
    (comp (ref "R5")
      (value "10k")
      (footprint "eagle-import:R0805")
      (fields (field (name "PARTNO") "311-10KARCT-ND"))
      (libsource (lib "eagle-import") (part "R-EU_R0805"))
    )
    (comp (ref "R6")
      (value "1.5K")
      (footprint "eagle-import:R0805")
      (fields (field (name "PARTNO") "311-1.5KARCT-ND"))
      (libsource (lib "eagle-import") (part "R-EU_R0805"))
    )
    (comp (ref "R7")
      (value "22K")
      (footprint "eagle-import:R0805")
      (fields (field (name "PARTNO") "311-22KARCT-ND"))
      (libsource (lib "eagle-import") (part "R-EU_R0805"))
    )
    (comp (ref "R8")
      (value "27")
      (footprint "eagle-import:R0805")
      (fields (field (name "PARTNO") "311-27ARCT-ND"))
      (libsource (lib "eagle-import") (part "R-EU_R0805"))
    )
    (comp (ref "RN2")
      (value "27")
      (footprint "eagle-import:EXBV4V")
      (fields (field (name "PARTNO") "Y2270CT-ND"))
      (libsource (lib "eagle-import") (part "EXBV4V"))
    )
    (comp (ref "USB_HOST")
      (value "USB_MICROB")
      (footprint "eagle-import:USB_MICROB_PACKAGE")
      (fields (field (name "PARTNO") "H11634CT-ND"))
      (libsource (lib "eagle-import") (part "USB_MICROB"))
    )
  )
  (nets
    (net (code "24") (name "+3V3") (class "Default")
      (node (ref "C100") (pin "1") (pinfunction "1_1") (pintype "passive"))
      (node (ref "C101") (pin "1") (pinfunction "1_1") (pintype "passive"))
      (node (ref "C106") (pin "2") (pinfunction "2_2") (pintype "passive"))
      (node (ref "C111") (pin "2") (pinfunction "2_2") (pintype "passive"))
      (node (ref "C116") (pin "2") (pinfunction "2_2") (pintype "passive"))
      (node (ref "C19") (pin "2") (pinfunction "2_2") (pintype "passive"))
      (node (ref "C25") (pin "2") (pinfunction "2_2") (pintype "passive"))
      (node (ref "C30") (pin "2") (pinfunction "2_2") (pintype "passive"))
      (node (ref "C35") (pin "2") (pinfunction "2_2") (pintype "passive"))
      (node (ref "C36") (pin "2") (pinfunction "2_2") (pintype "passive"))
      (node (ref "C41") (pin "1") (pinfunction "1_1") (pintype "passive"))
      (node (ref "C42") (pin "1") (pinfunction "1_1") (pintype "passive"))
      (node (ref "C43") (pin "1") (pinfunction "1_1") (pintype "passive"))
      (node (ref "C44") (pin "1") (pinfunction "1_1") (pintype "passive"))
      (node (ref "C45") (pin "1") (pinfunction "1_1") (pintype "passive"))
      (node (ref "C46") (pin "2") (pinfunction "2_2") (pintype "passive"))
      (node (ref "C47") (pin "2") (pinfunction "2_2") (pintype "passive"))
      (node (ref "C58") (pin "2") (pinfunction "2_2") (pintype "passive"))
      (node (ref "C6") (pin "1") (pinfunction "1_1") (pintype "passive"))
      (node (ref "C62") (pin "1") (pinfunction "1_1") (pintype "passive"))
      (node (ref "C63") (pin "1") (pinfunction "1_1") (pintype "passive"))
      (node (ref "C64") (pin "1") (pinfunction "1_1") (pintype "passive"))
      (node (ref "C65") (pin "1") (pinfunction "1_1") (pintype "passive"))
      (node (ref "C66") (pin "1") (pinfunction "1_1") (pintype "passive"))
      (node (ref "C7") (pin "1") (pinfunction "1_1") (pintype "passive"))
      (node (ref "C71") (pin "2") (pinfunction "2_2") (pintype "passive"))
      (node (ref "C76") (pin "2") (pinfunction "2_2") (pintype "passive"))
      (node (ref "C81") (pin "2") (pinfunction "2_2") (pintype "passive"))
      (node (ref "C93") (pin "2") (pinfunction "2_2") (pintype "passive"))
      (node (ref "C97") (pin "1") (pinfunction "1_1") (pintype "passive"))
      (node (ref "C98") (pin "1") (pinfunction "1_1") (pintype "passive"))
      (node (ref "C99") (pin "1") (pinfunction "1_1") (pintype "passive"))
      (node (ref "FB1") (pin "1") (pinfunction "1_1") (pintype "passive"))
      (node (ref "FB2") (pin "1") (pinfunction "1_1") (pintype "passive"))
      (node (ref "FB2\\") (pin "1") (pinfunction "1_1") (pintype "passive"))
      (node (ref "FB2\\1") (pin "1") (pinfunction "1_1") (pintype "passive"))
      (node (ref "FB2\\2") (pin "1") (pinfunction "1_1") (pintype "passive"))
      (node (ref "FB3") (pin "1") (pinfunction "1_1") (pintype "passive"))
      (node (ref "FTDI1") (pin "20") (pinfunction "VCCIO_20") (pintype "power_in"))
      (node (ref "FTDI1") (pin "31") (pinfunction "VCCIO_31") (pintype "power_in"))
      (node (ref "FTDI1") (pin "42") (pinfunction "VCCIO_42") (pintype "power_in"))
      (node (ref "FTDI1") (pin "50") (pinfunction "VREGIN_50") (pintype "bidirectional"))
      (node (ref "FTDI1") (pin "56") (pinfunction "VCCIO_56") (pintype "power_in"))
      (node (ref "FTDI2") (pin "20") (pinfunction "VCCIO_20") (pintype "power_in"))
      (node (ref "FTDI2") (pin "31") (pinfunction "VCCIO_31") (pintype "power_in"))
      (node (ref "FTDI2") (pin "42") (pinfunction "VCCIO_42") (pintype "power_in"))
      (node (ref "FTDI2") (pin "50") (pinfunction "VREGIN_50") (pintype "bidirectional"))
      (node (ref "FTDI2") (pin "56") (pinfunction "VCCIO_56") (pintype "power_in"))
      (node (ref "FTDI3") (pin "20") (pinfunction "VCCIO_20") (pintype "power_in"))
      (node (ref "FTDI3") (pin "31") (pinfunction "VCCIO_31") (pintype "power_in"))
      (node (ref "FTDI3") (pin "42") (pinfunction "VCCIO_42") (pintype "power_in"))
      (node (ref "FTDI3") (pin "50") (pinfunction "VREGIN_50") (pintype "bidirectional"))
      (node (ref "FTDI3") (pin "56") (pinfunction "VCCIO_56") (pintype "power_in"))
      (node (ref "HUB") (pin "10") (pinfunction "~{OVRCUR1}_10") (pintype "input"))
      (node (ref "HUB") (pin "14") (pinfunction "~{OVRCUR2}_14") (pintype "input"))
      (node (ref "HUB") (pin "18") (pinfunction "~{OVRCUR3}_18") (pintype "input"))
      (node (ref "HUB") (pin "22") (pinfunction "~{OVRCUR4}_22") (pintype "input"))
      (node (ref "HUB") (pin "25") (pinfunction "VCC_25") (pintype "power_in"))
      (node (ref "HUB") (pin "26") (pinfunction "~{EXTMEM}_26") (pintype "input"))
      (node (ref "HUB") (pin "3") (pinfunction "VCC_3") (pintype "power_in"))
      (node (ref "IC10") (pin "16") (pinfunction "VCC_16") (pintype "power_in"))
      (node (ref "IC11") (pin "16") (pinfunction "VCC_16") (pintype "power_in"))
      (node (ref "IC12") (pin "16") (pinfunction "VCC_16") (pintype "power_in"))
      (node (ref "IC13") (pin "16") (pinfunction "VCC_16") (pintype "power_in"))
      (node (ref "IC15") (pin "16") (pinfunction "VCC_16") (pintype "power_in"))
      (node (ref "IC16") (pin "16") (pinfunction "VCC_16") (pintype "power_in"))
      (node (ref "IC17") (pin "16") (pinfunction "VCC_16") (pintype "power_in"))
      (node (ref "IC18") (pin "16") (pinfunction "VCC_16") (pintype "power_in"))
      (node (ref "IC5") (pin "16") (pinfunction "VCC_16") (pintype "power_in"))
      (node (ref "IC6") (pin "16") (pinfunction "VCC_16") (pintype "power_in"))
      (node (ref "IC7") (pin "16") (pinfunction "VCC_16") (pintype "power_in"))
      (node (ref "IC8") (pin "16") (pinfunction "VCC_16") (pintype "power_in"))
      (node (ref "L3") (pin "2") (pinfunction "2_2") (pintype "passive"))
      (node (ref "QG1") (pin "1") (pinfunction "TS_1") (pintype "passive"))
      (node (ref "QG1") (pin "4") (pinfunction "VCC_4") (pintype "power_in"))
      (node (ref "R4") (pin "1") (pinfunction "1_1") (pintype "passive"))
      (node (ref "R6") (pin "1") (pinfunction "1_1") (pintype "passive"))
      (node (ref "R7") (pin "2") (pinfunction "2_2") (pintype "passive"))
    )
    (net (code "25") (name "+5V") (class "Default")
      (node (ref "C2") (pin "1") (pinfunction "1_1") (pintype "passive"))
      (node (ref "C3") (pin "1") (pinfunction "1_1") (pintype "passive"))
      (node (ref "DAISY_IN") (pin "1") (pinfunction "1_1") (pintype "passive"))
      (node (ref "DAISY_OUT") (pin "1") (pinfunction "1_1") (pintype "passive"))
      (node (ref "IC1") (pin "3") (pinfunction "EN_3") (pintype "input"))
      (node (ref "IC1") (pin "4") (pinfunction "VIN_4") (pintype "input"))
      (node (ref "PWRIN") (pin "1") (pinfunction "1_1") (pintype "passive"))
    )
    (net (code "34") (name "12MHZ") (class "Default")
      (node (ref "FTDI1") (pin "2") (pinfunction "XTIN_2") (pintype "input"))
      (node (ref "FTDI2") (pin "2") (pinfunction "XTIN_2") (pintype "input"))
      (node (ref "FTDI3") (pin "2") (pinfunction "XTIN_2") (pintype "input"))
      (node (ref "QG1") (pin "3") (pinfunction "OUT_3") (pintype "output"))
    )
    (net (code "35") (name "CTS1E") (class "Default")
      (node (ref "IC5") (pin "8") (pinfunction "RIN2_8") (pintype "input"))
      (node (ref "U$1") (pin "P4.8") (pinfunction "8_P4.8") (pintype "passive"))
    )
    (net (code "36") (name "CTS1E1") (class "Default")
      (node (ref "IC10") (pin "8") (pinfunction "RIN2_8") (pintype "input"))
      (node (ref "U$1") (pin "P8.8") (pinfunction "8_P8.8") (pintype "passive"))
    )
    (net (code "37") (name "CTS1E2") (class "Default")
      (node (ref "IC15") (pin "8") (pinfunction "RIN2_8") (pintype "input"))
      (node (ref "U$1") (pin "P12.8") (pinfunction "8_P12.8") (pintype "passive"))
    )
    (net (code "38") (name "CTS1I") (class "Default")
      (node (ref "FTDI1") (pin "19") (pinfunction "DB3/CTS_19") (pintype "bidirectional"))
      (node (ref "IC5") (pin "9") (pinfunction "ROUT2_9") (pintype "output"))
    )
    (net (code "39") (name "CTS1I1") (class "Default")
      (node (ref "FTDI2") (pin "19") (pinfunction "DB3/CTS_19") (pintype "bidirectional"))
      (node (ref "IC10") (pin "9") (pinfunction "ROUT2_9") (pintype "output"))
    )
    (net (code "40") (name "CTS1I2") (class "Default")
      (node (ref "FTDI3") (pin "19") (pinfunction "DB3/CTS_19") (pintype "bidirectional"))
      (node (ref "IC15") (pin "9") (pinfunction "ROUT2_9") (pintype "output"))
    )
    (net (code "41") (name "CTS2E") (class "Default")
      (node (ref "IC6") (pin "8") (pinfunction "RIN2_8") (pintype "input"))
      (node (ref "U$1") (pin "P3.8") (pinfunction "8_P3.8") (pintype "passive"))
    )
    (net (code "42") (name "CTS2E1") (class "Default")
      (node (ref "IC11") (pin "8") (pinfunction "RIN2_8") (pintype "input"))
      (node (ref "U$1") (pin "P7.8") (pinfunction "8_P7.8") (pintype "passive"))
    )
    (net (code "43") (name "CTS2E2") (class "Default")
      (node (ref "IC16") (pin "8") (pinfunction "RIN2_8") (pintype "input"))
      (node (ref "U$1") (pin "P11.8") (pinfunction "8_P11.8") (pintype "passive"))
    )
    (net (code "44") (name "CTS2I") (class "Default")
      (node (ref "FTDI1") (pin "29") (pinfunction "DB3/CTS_29") (pintype "bidirectional"))
      (node (ref "IC6") (pin "9") (pinfunction "ROUT2_9") (pintype "output"))
    )
    (net (code "45") (name "CTS2I1") (class "Default")
      (node (ref "FTDI2") (pin "29") (pinfunction "DB3/CTS_29") (pintype "bidirectional"))
      (node (ref "IC11") (pin "9") (pinfunction "ROUT2_9") (pintype "output"))
    )
    (net (code "46") (name "CTS2I2") (class "Default")
      (node (ref "FTDI3") (pin "29") (pinfunction "DB3/CTS_29") (pintype "bidirectional"))
      (node (ref "IC16") (pin "9") (pinfunction "ROUT2_9") (pintype "output"))
    )
    (net (code "47") (name "CTS3E") (class "Default")
      (node (ref "IC7") (pin "8") (pinfunction "RIN2_8") (pintype "input"))
      (node (ref "U$1") (pin "P2.8") (pinfunction "8_P2.8") (pintype "passive"))
    )
    (net (code "48") (name "CTS3E1") (class "Default")
      (node (ref "IC12") (pin "8") (pinfunction "RIN2_8") (pintype "input"))
      (node (ref "U$1") (pin "P6.8") (pinfunction "8_P6.8") (pintype "passive"))
    )
    (net (code "49") (name "CTS3E2") (class "Default")
      (node (ref "IC17") (pin "8") (pinfunction "RIN2_8") (pintype "input"))
      (node (ref "U$1") (pin "P10.8") (pinfunction "8_P10.8") (pintype "passive"))
    )
    (net (code "50") (name "CTS3I") (class "Default")
      (node (ref "FTDI1") (pin "41") (pinfunction "DB3/CTS_41") (pintype "bidirectional"))
      (node (ref "IC7") (pin "9") (pinfunction "ROUT2_9") (pintype "output"))
    )
    (net (code "51") (name "CTS3I1") (class "Default")
      (node (ref "FTDI2") (pin "41") (pinfunction "DB3/CTS_41") (pintype "bidirectional"))
      (node (ref "IC12") (pin "9") (pinfunction "ROUT2_9") (pintype "output"))
    )
    (net (code "52") (name "CTS3I2") (class "Default")
      (node (ref "FTDI3") (pin "41") (pinfunction "DB3/CTS_41") (pintype "bidirectional"))
      (node (ref "IC17") (pin "9") (pinfunction "ROUT2_9") (pintype "output"))
    )
    (net (code "53") (name "CTS4E") (class "Default")
      (node (ref "IC8") (pin "8") (pinfunction "RIN2_8") (pintype "input"))
      (node (ref "U$1") (pin "P1.8") (pinfunction "8_P1.8") (pintype "passive"))
    )
    (net (code "54") (name "CTS4E1") (class "Default")
      (node (ref "IC13") (pin "8") (pinfunction "RIN2_8") (pintype "input"))
      (node (ref "U$1") (pin "P5.8") (pinfunction "8_P5.8") (pintype "passive"))
    )
    (net (code "55") (name "CTS4E2") (class "Default")
      (node (ref "IC18") (pin "8") (pinfunction "RIN2_8") (pintype "input"))
      (node (ref "U$1") (pin "P9.8") (pinfunction "8_P9.8") (pintype "passive"))
    )
    (net (code "56") (name "CTS4I") (class "Default")
      (node (ref "FTDI1") (pin "54") (pinfunction "DB3/CTS_54") (pintype "bidirectional"))
      (node (ref "IC8") (pin "9") (pinfunction "ROUT2_9") (pintype "output"))
    )
    (net (code "57") (name "CTS4I1") (class "Default")
      (node (ref "FTDI2") (pin "54") (pinfunction "DB3/CTS_54") (pintype "bidirectional"))
      (node (ref "IC13") (pin "9") (pinfunction "ROUT2_9") (pintype "output"))
    )
    (net (code "58") (name "CTS4I2") (class "Default")
      (node (ref "FTDI3") (pin "54") (pinfunction "DB3/CTS_54") (pintype "bidirectional"))
      (node (ref "IC18") (pin "9") (pinfunction "ROUT2_9") (pintype "output"))
    )
    (net (code "59") (name "D0_N") (class "Default")
      (node (ref "D1") (pin "4") (pinfunction "B_4") (pintype "passive"))
      (node (ref "HUB") (pin "2") (pinfunction "DM0_2") (pintype "bidirectional"))
      (node (ref "R1") (pin "1") (pinfunction "1_1") (pintype "passive"))
    )
    (net (code "60") (name "D0_P") (class "Default")
      (node (ref "D1") (pin "6") (pinfunction "A_6") (pintype "passive"))
      (node (ref "HUB") (pin "1") (pinfunction "DP0_1") (pintype "bidirectional"))
      (node (ref "R6") (pin "2") (pinfunction "2_2") (pintype "passive"))
      (node (ref "R8") (pin "1") (pinfunction "1_1") (pintype "passive"))
    )
    (net (code "61") (name "D1_N") (class "Default")
      (node (ref "D2") (pin "4") (pinfunction "B_4") (pintype "passive"))
      (node (ref "HUB") (pin "23") (pinfunction "DM4_23") (pintype "bidirectional"))
      (node (ref "RN2") (pin "B1") (pinfunction "1_B1") (pintype "passive"))
    )
    (net (code "62") (name "D1_P") (class "Default")
      (node (ref "D2") (pin "6") (pinfunction "A_6") (pintype "passive"))
      (node (ref "HUB") (pin "24") (pinfunction "DP4_24") (pintype "bidirectional"))
      (node (ref "RN2") (pin "A1") (pinfunction "1_A1") (pintype "passive"))
    )
    (net (code "63") (name "D2_N") (class "Default")
      (node (ref "FTDI1") (pin "7") (pinfunction "USBDM_7") (pintype "input"))
      (node (ref "HUB") (pin "11") (pinfunction "DM1_11") (pintype "bidirectional"))
    )
    (net (code "64") (name "D2_P") (class "Default")
      (node (ref "FTDI1") (pin "8") (pinfunction "USBDP_8") (pintype "input"))
      (node (ref "HUB") (pin "12") (pinfunction "DP1_12") (pintype "bidirectional"))
    )
    (net (code "65") (name "D3_N") (class "Default")
      (node (ref "FTDI2") (pin "7") (pinfunction "USBDM_7") (pintype "input"))
      (node (ref "HUB") (pin "15") (pinfunction "DM2_15") (pintype "bidirectional"))
    )
    (net (code "66") (name "D3_P") (class "Default")
      (node (ref "FTDI2") (pin "8") (pinfunction "USBDP_8") (pintype "input"))
      (node (ref "HUB") (pin "16") (pinfunction "DP2_16") (pintype "bidirectional"))
    )
    (net (code "67") (name "D4_N") (class "Default")
      (node (ref "FTDI3") (pin "7") (pinfunction "USBDM_7") (pintype "input"))
      (node (ref "HUB") (pin "19") (pinfunction "DM3_19") (pintype "bidirectional"))
    )
    (net (code "68") (name "D4_P") (class "Default")
      (node (ref "FTDI3") (pin "8") (pinfunction "USBDP_8") (pintype "input"))
      (node (ref "HUB") (pin "20") (pinfunction "DP3_20") (pintype "bidirectional"))
    )
    (net (code "69") (name "ETXN") (class "Default")
      (node (ref "U$1") (pin "P12.2") (pinfunction "2_P12.2") (pintype "passive"))
      (node (ref "X1") (pin "2") (pinfunction "7_2") (pintype "passive"))
    )
    (net (code "70") (name "GND") (class "Default")
      (node (ref "C100") (pin "2") (pinfunction "2_2") (pintype "passive"))
      (node (ref "C101") (pin "2") (pinfunction "2_2") (pintype "passive"))
      (node (ref "C104") (pin "1") (pinfunction "1_1") (pintype "passive"))
      (node (ref "C105") (pin "1") (pinfunction "1_1") (pintype "passive"))
      (node (ref "C106") (pin "1") (pinfunction "1_1") (pintype "passive"))
      (node (ref "C109") (pin "1") (pinfunction "1_1") (pintype "passive"))
      (node (ref "C11") (pin "2") (pinfunction "2_2") (pintype "passive"))
      (node (ref "C110") (pin "1") (pinfunction "1_1") (pintype "passive"))
      (node (ref "C111") (pin "1") (pinfunction "1_1") (pintype "passive"))
      (node (ref "C114") (pin "1") (pinfunction "1_1") (pintype "passive"))
      (node (ref "C115") (pin "1") (pinfunction "1_1") (pintype "passive"))
      (node (ref "C116") (pin "1") (pinfunction "1_1") (pintype "passive"))
      (node (ref "C12") (pin "2") (pinfunction "2_2") (pintype "passive"))
      (node (ref "C13") (pin "2") (pinfunction "2_2") (pintype "passive"))
      (node (ref "C14") (pin "2") (pinfunction "2_2") (pintype "passive"))
      (node (ref "C17") (pin "1") (pinfunction "1_1") (pintype "passive"))
      (node (ref "C18") (pin "1") (pinfunction "1_1") (pintype "passive"))
      (node (ref "C19") (pin "1") (pinfunction "1_1") (pintype "passive"))
      (node (ref "C2") (pin "2") (pinfunction "2_2") (pintype "passive"))
      (node (ref "C20") (pin "1") (pinfunction "1_1") (pintype "passive"))
      (node (ref "C21") (pin "1") (pinfunction "1_1") (pintype "passive"))
      (node (ref "C23") (pin "1") (pinfunction "1_1") (pintype "passive"))
      (node (ref "C24") (pin "1") (pinfunction "1_1") (pintype "passive"))
      (node (ref "C25") (pin "1") (pinfunction "1_1") (pintype "passive"))
      (node (ref "C28") (pin "1") (pinfunction "1_1") (pintype "passive"))
      (node (ref "C29") (pin "1") (pinfunction "1_1") (pintype "passive"))
      (node (ref "C3") (pin "2") (pinfunction "2_2") (pintype "passive"))
      (node (ref "C30") (pin "1") (pinfunction "1_1") (pintype "passive"))
      (node (ref "C33") (pin "1") (pinfunction "1_1") (pintype "passive"))
      (node (ref "C34") (pin "1") (pinfunction "1_1") (pintype "passive"))
      (node (ref "C35") (pin "1") (pinfunction "1_1") (pintype "passive"))
      (node (ref "C36") (pin "1") (pinfunction "1_1") (pintype "passive"))
      (node (ref "C37") (pin "1") (pinfunction "1_1") (pintype "passive"))
      (node (ref "C38") (pin "2") (pinfunction "2_2") (pintype "passive"))
      (node (ref "C39") (pin "2") (pinfunction "2_2") (pintype "passive"))
      (node (ref "C40") (pin "2") (pinfunction "2_2") (pintype "passive"))
      (node (ref "C41") (pin "2") (pinfunction "2_2") (pintype "passive"))
      (node (ref "C42") (pin "2") (pinfunction "2_2") (pintype "passive"))
      (node (ref "C43") (pin "2") (pinfunction "2_2") (pintype "passive"))
      (node (ref "C44") (pin "2") (pinfunction "2_2") (pintype "passive"))
      (node (ref "C45") (pin "2") (pinfunction "2_2") (pintype "passive"))
      (node (ref "C46") (pin "1") (pinfunction "1_1") (pintype "passive"))
      (node (ref "C47") (pin "1") (pinfunction "1_1") (pintype "passive"))
      (node (ref "C489") (pin "2") (pinfunction "2_2") (pintype "passive"))
      (node (ref "C5") (pin "2") (pinfunction "2_2") (pintype "passive"))
      (node (ref "C502") (pin "2") (pinfunction "2_2") (pintype "passive"))
      (node (ref "C519") (pin "2") (pinfunction "2_2") (pintype "passive"))
      (node (ref "C53") (pin "2") (pinfunction "2_2") (pintype "passive"))
      (node (ref "C56") (pin "1") (pinfunction "1_1") (pintype "passive"))
      (node (ref "C57") (pin "1") (pinfunction "1_1") (pintype "passive"))
      (node (ref "C58") (pin "1") (pinfunction "1_1") (pintype "passive"))
      (node (ref "C59") (pin "2") (pinfunction "2_2") (pintype "passive"))
      (node (ref "C6") (pin "2") (pinfunction "2_2") (pintype "passive"))
      (node (ref "C60") (pin "2") (pinfunction "2_2") (pintype "passive"))
      (node (ref "C61") (pin "2") (pinfunction "2_2") (pintype "passive"))
      (node (ref "C62") (pin "2") (pinfunction "2_2") (pintype "passive"))
      (node (ref "C629") (pin "1") (pinfunction "1_1") (pintype "passive"))
      (node (ref "C63") (pin "2") (pinfunction "2_2") (pintype "passive"))
      (node (ref "C64") (pin "2") (pinfunction "2_2") (pintype "passive"))
      (node (ref "C65") (pin "2") (pinfunction "2_2") (pintype "passive"))
      (node (ref "C66") (pin "2") (pinfunction "2_2") (pintype "passive"))
      (node (ref "C69") (pin "1") (pinfunction "1_1") (pintype "passive"))
      (node (ref "C7") (pin "2") (pinfunction "2_2") (pintype "passive"))
      (node (ref "C70") (pin "1") (pinfunction "1_1") (pintype "passive"))
      (node (ref "C71") (pin "1") (pinfunction "1_1") (pintype "passive"))
      (node (ref "C74") (pin "1") (pinfunction "1_1") (pintype "passive"))
      (node (ref "C75") (pin "1") (pinfunction "1_1") (pintype "passive"))
      (node (ref "C76") (pin "1") (pinfunction "1_1") (pintype "passive"))
      (node (ref "C79") (pin "1") (pinfunction "1_1") (pintype "passive"))
      (node (ref "C8") (pin "1") (pinfunction "1_1") (pintype "passive"))
      (node (ref "C80") (pin "1") (pinfunction "1_1") (pintype "passive"))
      (node (ref "C81") (pin "1") (pinfunction "1_1") (pintype "passive"))
      (node (ref "C829") (pin "1") (pinfunction "1_1") (pintype "passive"))
      (node (ref "C859") (pin "2") (pinfunction "2_2") (pintype "passive"))
      (node (ref "C869") (pin "2") (pinfunction "2_2") (pintype "passive"))
      (node (ref "C879") (pin "2") (pinfunction "2_2") (pintype "passive"))
      (node (ref "C889") (pin "2") (pinfunction "2_2") (pintype "passive"))
      (node (ref "C91") (pin "1") (pinfunction "1_1") (pintype "passive"))
      (node (ref "C92") (pin "1") (pinfunction "1_1") (pintype "passive"))
      (node (ref "C93") (pin "1") (pinfunction "1_1") (pintype "passive"))
      (node (ref "C94") (pin "2") (pinfunction "2_2") (pintype "passive"))
      (node (ref "C95") (pin "2") (pinfunction "2_2") (pintype "passive"))
      (node (ref "C96") (pin "2") (pinfunction "2_2") (pintype "passive"))
      (node (ref "C97") (pin "2") (pinfunction "2_2") (pintype "passive"))
      (node (ref "C98") (pin "2") (pinfunction "2_2") (pintype "passive"))
      (node (ref "C99") (pin "2") (pinfunction "2_2") (pintype "passive"))
      (node (ref "D1") (pin "2") (pinfunction "GND_2") (pintype "power_in"))
      (node (ref "D1") (pin "5") (pinfunction "GND_5") (pintype "power_in"))
      (node (ref "D2") (pin "2") (pinfunction "GND_2") (pintype "power_in"))
      (node (ref "D2") (pin "5") (pinfunction "GND_5") (pintype "power_in"))
      (node (ref "DAISY_IN") (pin "4") (pinfunction "4_4") (pintype "passive"))
      (node (ref "DAISY_OUT") (pin "4") (pinfunction "4_4") (pintype "passive"))
      (node (ref "FTDI1") (pin "1") (pinfunction "GND_1") (pintype "power_in"))
      (node (ref "FTDI1") (pin "10") (pinfunction "AGND_10") (pintype "power_in"))
      (node (ref "FTDI1") (pin "11") (pinfunction "GND_11") (pintype "power_in"))
      (node (ref "FTDI1") (pin "13") (pinfunction "TEST_13") (pintype "input"))
      (node (ref "FTDI1") (pin "15") (pinfunction "GND_15") (pintype "power_in"))
      (node (ref "FTDI1") (pin "25") (pinfunction "GND_25") (pintype "power_in"))
      (node (ref "FTDI1") (pin "35") (pinfunction "GND_35") (pintype "power_in"))
      (node (ref "FTDI1") (pin "47") (pinfunction "GND_47") (pintype "power_in"))
      (node (ref "FTDI1") (pin "5") (pinfunction "GND_5") (pintype "power_in"))
      (node (ref "FTDI1") (pin "51") (pinfunction "GND_51") (pintype "power_in"))
      (node (ref "FTDI2") (pin "1") (pinfunction "GND_1") (pintype "power_in"))
      (node (ref "FTDI2") (pin "10") (pinfunction "AGND_10") (pintype "power_in"))
      (node (ref "FTDI2") (pin "11") (pinfunction "GND_11") (pintype "power_in"))
      (node (ref "FTDI2") (pin "13") (pinfunction "TEST_13") (pintype "input"))
      (node (ref "FTDI2") (pin "15") (pinfunction "GND_15") (pintype "power_in"))
      (node (ref "FTDI2") (pin "25") (pinfunction "GND_25") (pintype "power_in"))
      (node (ref "FTDI2") (pin "35") (pinfunction "GND_35") (pintype "power_in"))
      (node (ref "FTDI2") (pin "47") (pinfunction "GND_47") (pintype "power_in"))
      (node (ref "FTDI2") (pin "5") (pinfunction "GND_5") (pintype "power_in"))
      (node (ref "FTDI2") (pin "51") (pinfunction "GND_51") (pintype "power_in"))
      (node (ref "FTDI3") (pin "1") (pinfunction "GND_1") (pintype "power_in"))
      (node (ref "FTDI3") (pin "10") (pinfunction "AGND_10") (pintype "power_in"))
      (node (ref "FTDI3") (pin "11") (pinfunction "GND_11") (pintype "power_in"))
      (node (ref "FTDI3") (pin "13") (pinfunction "TEST_13") (pintype "input"))
      (node (ref "FTDI3") (pin "15") (pinfunction "GND_15") (pintype "power_in"))
      (node (ref "FTDI3") (pin "25") (pinfunction "GND_25") (pintype "power_in"))
      (node (ref "FTDI3") (pin "35") (pinfunction "GND_35") (pintype "power_in"))
      (node (ref "FTDI3") (pin "47") (pinfunction "GND_47") (pintype "power_in"))
      (node (ref "FTDI3") (pin "5") (pinfunction "GND_5") (pintype "power_in"))
      (node (ref "FTDI3") (pin "51") (pinfunction "GND_51") (pintype "power_in"))
      (node (ref "HUB") (pin "27") (pinfunction "TSTPLL/48MCLK_27") (pintype "bidirectional"))
      (node (ref "HUB") (pin "28") (pinfunction "GND_28") (pintype "passive"))
      (node (ref "HUB") (pin "31") (pinfunction "TSTMODE_31") (pintype "input"))
      (node (ref "HUB") (pin "7") (pinfunction "GND_7") (pintype "passive"))
      (node (ref "HUB") (pin "8") (pinfunction "BUSPWR_8") (pintype "input"))
      (node (ref "IC1") (pin "5") (pinfunction "GND_5") (pintype "passive"))
      (node (ref "IC1") (pin "8") (pinfunction "AGND_8") (pintype "passive"))
      (node (ref "IC10") (pin "15") (pinfunction "GND_15") (pintype "passive"))
      (node (ref "IC11") (pin "15") (pinfunction "GND_15") (pintype "passive"))
      (node (ref "IC12") (pin "15") (pinfunction "GND_15") (pintype "passive"))
      (node (ref "IC13") (pin "15") (pinfunction "GND_15") (pintype "passive"))
      (node (ref "IC15") (pin "15") (pinfunction "GND_15") (pintype "passive"))
      (node (ref "IC16") (pin "15") (pinfunction "GND_15") (pintype "passive"))
      (node (ref "IC17") (pin "15") (pinfunction "GND_15") (pintype "passive"))
      (node (ref "IC18") (pin "15") (pinfunction "GND_15") (pintype "passive"))
      (node (ref "IC5") (pin "15") (pinfunction "GND_15") (pintype "passive"))
      (node (ref "IC6") (pin "15") (pinfunction "GND_15") (pintype "passive"))
      (node (ref "IC7") (pin "15") (pinfunction "GND_15") (pintype "passive"))
      (node (ref "IC8") (pin "15") (pinfunction "GND_15") (pintype "passive"))
      (node (ref "PWRIN") (pin "2") (pinfunction "2_2") (pintype "passive"))
      (node (ref "QG1") (pin "2") (pinfunction "GND_2") (pintype "power_in"))
      (node (ref "R13") (pin "1") (pinfunction "1_1") (pintype "passive"))
      (node (ref "R15") (pin "1") (pinfunction "1_1") (pintype "passive"))
      (node (ref "R2") (pin "1") (pinfunction "1_1") (pintype "passive"))
      (node (ref "R5") (pin "2") (pinfunction "2_2") (pintype "passive"))
      (node (ref "U$1") (pin "P1.4") (pinfunction "4_P1.4") (pintype "passive"))
      (node (ref "U$1") (pin "P1.5") (pinfunction "5_P1.5") (pintype "passive"))
      (node (ref "U$1") (pin "P10.4") (pinfunction "4_P10.4") (pintype "passive"))
      (node (ref "U$1") (pin "P10.5") (pinfunction "5_P10.5") (pintype "passive"))
      (node (ref "U$1") (pin "P11.4") (pinfunction "4_P11.4") (pintype "passive"))
      (node (ref "U$1") (pin "P11.5") (pinfunction "5_P11.5") (pintype "passive"))
      (node (ref "U$1") (pin "P12.4") (pinfunction "4_P12.4") (pintype "passive"))
      (node (ref "U$1") (pin "P12.5") (pinfunction "5_P12.5") (pintype "passive"))
      (node (ref "U$1") (pin "P2.4") (pinfunction "4_P2.4") (pintype "passive"))
      (node (ref "U$1") (pin "P2.5") (pinfunction "5_P2.5") (pintype "passive"))
      (node (ref "U$1") (pin "P3.4") (pinfunction "4_P3.4") (pintype "passive"))
      (node (ref "U$1") (pin "P3.5") (pinfunction "5_P3.5") (pintype "passive"))
      (node (ref "U$1") (pin "P4.4") (pinfunction "4_P4.4") (pintype "passive"))
      (node (ref "U$1") (pin "P4.5") (pinfunction "5_P4.5") (pintype "passive"))
      (node (ref "U$1") (pin "P5.4") (pinfunction "4_P5.4") (pintype "passive"))
      (node (ref "U$1") (pin "P5.5") (pinfunction "5_P5.5") (pintype "passive"))
      (node (ref "U$1") (pin "P6.4") (pinfunction "4_P6.4") (pintype "passive"))
      (node (ref "U$1") (pin "P6.5") (pinfunction "5_P6.5") (pintype "passive"))
      (node (ref "U$1") (pin "P7.4") (pinfunction "4_P7.4") (pintype "passive"))
      (node (ref "U$1") (pin "P7.5") (pinfunction "5_P7.5") (pintype "passive"))
      (node (ref "U$1") (pin "P8.4") (pinfunction "4_P8.4") (pintype "passive"))
      (node (ref "U$1") (pin "P8.5") (pinfunction "5_P8.5") (pintype "passive"))
      (node (ref "U$1") (pin "P9.4") (pinfunction "4_P9.4") (pintype "passive"))
      (node (ref "U$1") (pin "P9.5") (pinfunction "5_P9.5") (pintype "passive"))
      (node (ref "USB_HOST") (pin "GND") (pinfunction "GND_GND") (pintype "bidirectional"))
    )
    (net (code "71") (name "Net-(C21-Pad2)") (class "Default")
      (node (ref "C21") (pin "2") (pinfunction "2_2") (pintype "passive"))
      (node (ref "Q2") (pin "2") (pinfunction "2_2") (pintype "passive"))
      (node (ref "R3") (pin "2") (pinfunction "2_2") (pintype "passive"))
    )
    (net (code "72") (name "Net-(DAISY_OUT-Pad2)") (class "Default")
      (node (ref "DAISY_OUT") (pin "2") (pinfunction "2_2") (pintype "passive"))
      (node (ref "R8") (pin "2") (pinfunction "2_2") (pintype "passive"))
      (node (ref "USB_HOST") (pin "D+") (pinfunction "D+_D+") (pintype "bidirectional"))
    )
    (net (code "73") (name "Net-(DAISY_OUT-Pad3)") (class "Default")
      (node (ref "DAISY_OUT") (pin "3") (pinfunction "3_3") (pintype "passive"))
      (node (ref "R1") (pin "2") (pinfunction "2_2") (pintype "passive"))
      (node (ref "USB_HOST") (pin "D-") (pinfunction "D-_D-") (pintype "bidirectional"))
    )
    (net (code "74") (name "Net-(FTDI1D-REF)") (class "Default")
      (node (ref "FTDI1") (pin "6") (pinfunction "REF_6") (pintype "input"))
      (node (ref "R2") (pin "2") (pinfunction "2_2") (pintype "passive"))
    )
    (net (code "75") (name "Net-(FTDI1D-VPHY)") (class "Default")
      (node (ref "C11") (pin "1") (pinfunction "1_1") (pintype "passive"))
      (node (ref "C13") (pin "1") (pinfunction "1_1") (pintype "passive"))
      (node (ref "FB2\\") (pin "2") (pinfunction "2_2") (pintype "passive"))
      (node (ref "FTDI1") (pin "4") (pinfunction "VPHY_4") (pintype "power_in"))
    )
    (net (code "76") (name "Net-(FTDI1D-VPLL)") (class "Default")
      (node (ref "C12") (pin "1") (pinfunction "1_1") (pintype "passive"))
      (node (ref "C14") (pin "1") (pinfunction "1_1") (pintype "passive"))
      (node (ref "FB1") (pin "2") (pinfunction "2_2") (pintype "passive"))
      (node (ref "FTDI1") (pin "9") (pinfunction "VPLL_9") (pintype "power_in"))
    )
    (net (code "77") (name "Net-(FTDI1D-VREGOUT)") (class "Default")
      (node (ref "C38") (pin "1") (pinfunction "1_1") (pintype "passive"))
      (node (ref "C39") (pin "1") (pinfunction "1_1") (pintype "passive"))
      (node (ref "C40") (pin "1") (pinfunction "1_1") (pintype "passive"))
      (node (ref "C8") (pin "2") (pinfunction "2_2") (pintype "passive"))
      (node (ref "FTDI1") (pin "12") (pinfunction "VCORE_12") (pintype "power_in"))
      (node (ref "FTDI1") (pin "37") (pinfunction "VCORE_37") (pintype "power_in"))
      (node (ref "FTDI1") (pin "49") (pinfunction "VREGOUT_49") (pintype "output"))
      (node (ref "FTDI1") (pin "64") (pinfunction "VCORE_64") (pintype "power_in"))
    )
    (net (code "78") (name "Net-(FTDI2D-REF)") (class "Default")
      (node (ref "FTDI2") (pin "6") (pinfunction "REF_6") (pintype "input"))
      (node (ref "R13") (pin "2") (pinfunction "2_2") (pintype "passive"))
    )
    (net (code "79") (name "Net-(FTDI2D-VPHY)") (class "Default")
      (node (ref "C489") (pin "1") (pinfunction "1_1") (pintype "passive"))
      (node (ref "C502") (pin "1") (pinfunction "1_1") (pintype "passive"))
      (node (ref "FB2\\1") (pin "2") (pinfunction "2_2") (pintype "passive"))
      (node (ref "FTDI2") (pin "4") (pinfunction "VPHY_4") (pintype "power_in"))
    )
    (net (code "80") (name "Net-(FTDI2D-VPLL)") (class "Default")
      (node (ref "C519") (pin "1") (pinfunction "1_1") (pintype "passive"))
      (node (ref "C53") (pin "1") (pinfunction "1_1") (pintype "passive"))
      (node (ref "FB2") (pin "2") (pinfunction "2_2") (pintype "passive"))
      (node (ref "FTDI2") (pin "9") (pinfunction "VPLL_9") (pintype "power_in"))
    )
    (net (code "81") (name "Net-(FTDI2D-VREGOUT)") (class "Default")
      (node (ref "C59") (pin "1") (pinfunction "1_1") (pintype "passive"))
      (node (ref "C60") (pin "1") (pinfunction "1_1") (pintype "passive"))
      (node (ref "C61") (pin "1") (pinfunction "1_1") (pintype "passive"))
      (node (ref "C629") (pin "2") (pinfunction "2_2") (pintype "passive"))
      (node (ref "FTDI2") (pin "12") (pinfunction "VCORE_12") (pintype "power_in"))
      (node (ref "FTDI2") (pin "37") (pinfunction "VCORE_37") (pintype "power_in"))
      (node (ref "FTDI2") (pin "49") (pinfunction "VREGOUT_49") (pintype "output"))
      (node (ref "FTDI2") (pin "64") (pinfunction "VCORE_64") (pintype "power_in"))
    )
    (net (code "82") (name "Net-(FTDI3D-REF)") (class "Default")
      (node (ref "FTDI3") (pin "6") (pinfunction "REF_6") (pintype "input"))
      (node (ref "R15") (pin "2") (pinfunction "2_2") (pintype "passive"))
    )
    (net (code "83") (name "Net-(FTDI3D-VPHY)") (class "Default")
      (node (ref "C859") (pin "1") (pinfunction "1_1") (pintype "passive"))
      (node (ref "C879") (pin "1") (pinfunction "1_1") (pintype "passive"))
      (node (ref "FB2\\2") (pin "2") (pinfunction "2_2") (pintype "passive"))
      (node (ref "FTDI3") (pin "4") (pinfunction "VPHY_4") (pintype "power_in"))
    )
    (net (code "84") (name "Net-(FTDI3D-VPLL)") (class "Default")
      (node (ref "C869") (pin "1") (pinfunction "1_1") (pintype "passive"))
      (node (ref "C889") (pin "1") (pinfunction "1_1") (pintype "passive"))
      (node (ref "FB3") (pin "2") (pinfunction "2_2") (pintype "passive"))
      (node (ref "FTDI3") (pin "9") (pinfunction "VPLL_9") (pintype "power_in"))
    )
    (net (code "85") (name "Net-(FTDI3D-VREGOUT)") (class "Default")
      (node (ref "C829") (pin "2") (pinfunction "2_2") (pintype "passive"))
      (node (ref "C94") (pin "1") (pinfunction "1_1") (pintype "passive"))
      (node (ref "C95") (pin "1") (pinfunction "1_1") (pintype "passive"))
      (node (ref "C96") (pin "1") (pinfunction "1_1") (pintype "passive"))
      (node (ref "FTDI3") (pin "12") (pinfunction "VCORE_12") (pintype "power_in"))
      (node (ref "FTDI3") (pin "37") (pinfunction "VCORE_37") (pintype "power_in"))
      (node (ref "FTDI3") (pin "49") (pinfunction "VREGOUT_49") (pintype "output"))
      (node (ref "FTDI3") (pin "64") (pinfunction "VCORE_64") (pintype "power_in"))
    )
    (net (code "86") (name "Net-(HUB-XTAL1)") (class "Default")
      (node (ref "C20") (pin "2") (pinfunction "2_2") (pintype "passive"))
      (node (ref "HUB") (pin "30") (pinfunction "XTAL1_30") (pintype "input"))
      (node (ref "Q2") (pin "1") (pinfunction "1_1") (pintype "passive"))
    )
    (net (code "87") (name "Net-(HUB-XTAL2)") (class "Default")
      (node (ref "HUB") (pin "29") (pinfunction "XTAL2_29") (pintype "output"))
      (node (ref "R3") (pin "1") (pinfunction "1_1") (pintype "passive"))
    )
    (net (code "88") (name "Net-(IC1-BOOST)") (class "Default")
      (node (ref "C4") (pin "1") (pinfunction "1_1") (pintype "passive"))
      (node (ref "IC1") (pin "7") (pinfunction "BOOST_7") (pintype "passive"))
    )
    (net (code "89") (name "Net-(IC1-SW)") (class "Default")
      (node (ref "C4") (pin "2") (pinfunction "2_2") (pintype "passive"))
      (node (ref "IC1") (pin "6") (pinfunction "SW_6") (pintype "bidirectional"))
      (node (ref "L3") (pin "1") (pinfunction "1_1") (pintype "passive"))
    )
    (net (code "90") (name "Net-(IC1-VCC)") (class "Default")
      (node (ref "C5") (pin "1") (pinfunction "1_1") (pintype "passive"))
      (node (ref "IC1") (pin "2") (pinfunction "VCC_2") (pintype "passive"))
    )
    (net (code "91") (name "Net-(IC1-VFB)") (class "Default")
      (node (ref "IC1") (pin "1") (pinfunction "VFB_1") (pintype "input"))
      (node (ref "R4") (pin "2") (pinfunction "2_2") (pintype "passive"))
      (node (ref "R5") (pin "1") (pinfunction "1_1") (pintype "passive"))
    )
    (net (code "92") (name "Net-(IC5-C1+)") (class "Default")
      (node (ref "C15") (pin "2") (pinfunction "2_2") (pintype "passive"))
      (node (ref "IC5") (pin "1") (pinfunction "C1+_1") (pintype "passive"))
    )
    (net (code "93") (name "Net-(IC5-C1-)") (class "Default")
      (node (ref "C15") (pin "1") (pinfunction "1_1") (pintype "passive"))
      (node (ref "IC5") (pin "3") (pinfunction "C1-_3") (pintype "passive"))
    )
    (net (code "94") (name "Net-(IC5-C2+)") (class "Default")
      (node (ref "C16") (pin "2") (pinfunction "2_2") (pintype "passive"))
      (node (ref "IC5") (pin "4") (pinfunction "C2+_4") (pintype "passive"))
    )
    (net (code "95") (name "Net-(IC5-C2-)") (class "Default")
      (node (ref "C16") (pin "1") (pinfunction "1_1") (pintype "passive"))
      (node (ref "IC5") (pin "5") (pinfunction "C2-_5") (pintype "passive"))
    )
    (net (code "96") (name "Net-(IC5-V+)") (class "Default")
      (node (ref "C17") (pin "2") (pinfunction "2_2") (pintype "passive"))
      (node (ref "IC5") (pin "2") (pinfunction "V+_2") (pintype "power_in"))
    )
    (net (code "97") (name "Net-(IC5-V-)") (class "Default")
      (node (ref "C18") (pin "2") (pinfunction "2_2") (pintype "passive"))
      (node (ref "IC5") (pin "6") (pinfunction "V-_6") (pintype "power_in"))
    )
    (net (code "98") (name "Net-(IC6-C1+)") (class "Default")
      (node (ref "C1") (pin "2") (pinfunction "2_2") (pintype "passive"))
      (node (ref "IC6") (pin "1") (pinfunction "C1+_1") (pintype "passive"))
    )
    (net (code "99") (name "Net-(IC6-C1-)") (class "Default")
      (node (ref "C1") (pin "1") (pinfunction "1_1") (pintype "passive"))
      (node (ref "IC6") (pin "3") (pinfunction "C1-_3") (pintype "passive"))
    )
    (net (code "100") (name "Net-(IC6-C2+)") (class "Default")
      (node (ref "C22") (pin "2") (pinfunction "2_2") (pintype "passive"))
      (node (ref "IC6") (pin "4") (pinfunction "C2+_4") (pintype "passive"))
    )
    (net (code "101") (name "Net-(IC6-C2-)") (class "Default")
      (node (ref "C22") (pin "1") (pinfunction "1_1") (pintype "passive"))
      (node (ref "IC6") (pin "5") (pinfunction "C2-_5") (pintype "passive"))
    )
    (net (code "102") (name "Net-(IC6-V+)") (class "Default")
      (node (ref "C23") (pin "2") (pinfunction "2_2") (pintype "passive"))
      (node (ref "IC6") (pin "2") (pinfunction "V+_2") (pintype "power_in"))
    )
    (net (code "103") (name "Net-(IC6-V-)") (class "Default")
      (node (ref "C24") (pin "2") (pinfunction "2_2") (pintype "passive"))
      (node (ref "IC6") (pin "6") (pinfunction "V-_6") (pintype "power_in"))
    )
    (net (code "104") (name "Net-(IC7-C1+)") (class "Default")
      (node (ref "C26") (pin "2") (pinfunction "2_2") (pintype "passive"))
      (node (ref "IC7") (pin "1") (pinfunction "C1+_1") (pintype "passive"))
    )
    (net (code "105") (name "Net-(IC7-C1-)") (class "Default")
      (node (ref "C26") (pin "1") (pinfunction "1_1") (pintype "passive"))
      (node (ref "IC7") (pin "3") (pinfunction "C1-_3") (pintype "passive"))
    )
    (net (code "106") (name "Net-(IC7-C2+)") (class "Default")
      (node (ref "C27") (pin "2") (pinfunction "2_2") (pintype "passive"))
      (node (ref "IC7") (pin "4") (pinfunction "C2+_4") (pintype "passive"))
    )
    (net (code "107") (name "Net-(IC7-C2-)") (class "Default")
      (node (ref "C27") (pin "1") (pinfunction "1_1") (pintype "passive"))
      (node (ref "IC7") (pin "5") (pinfunction "C2-_5") (pintype "passive"))
    )
    (net (code "108") (name "Net-(IC7-V+)") (class "Default")
      (node (ref "C28") (pin "2") (pinfunction "2_2") (pintype "passive"))
      (node (ref "IC7") (pin "2") (pinfunction "V+_2") (pintype "power_in"))
    )
    (net (code "109") (name "Net-(IC7-V-)") (class "Default")
      (node (ref "C29") (pin "2") (pinfunction "2_2") (pintype "passive"))
      (node (ref "IC7") (pin "6") (pinfunction "V-_6") (pintype "power_in"))
    )
    (net (code "110") (name "Net-(IC8-C1+)") (class "Default")
      (node (ref "C31") (pin "2") (pinfunction "2_2") (pintype "passive"))
      (node (ref "IC8") (pin "1") (pinfunction "C1+_1") (pintype "passive"))
    )
    (net (code "111") (name "Net-(IC8-C1-)") (class "Default")
      (node (ref "C31") (pin "1") (pinfunction "1_1") (pintype "passive"))
      (node (ref "IC8") (pin "3") (pinfunction "C1-_3") (pintype "passive"))
    )
    (net (code "112") (name "Net-(IC8-C2+)") (class "Default")
      (node (ref "C32") (pin "2") (pinfunction "2_2") (pintype "passive"))
      (node (ref "IC8") (pin "4") (pinfunction "C2+_4") (pintype "passive"))
    )
    (net (code "113") (name "Net-(IC8-C2-)") (class "Default")
      (node (ref "C32") (pin "1") (pinfunction "1_1") (pintype "passive"))
      (node (ref "IC8") (pin "5") (pinfunction "C2-_5") (pintype "passive"))
    )
    (net (code "114") (name "Net-(IC8-V+)") (class "Default")
      (node (ref "C33") (pin "2") (pinfunction "2_2") (pintype "passive"))
      (node (ref "IC8") (pin "2") (pinfunction "V+_2") (pintype "power_in"))
    )
    (net (code "115") (name "Net-(IC8-V-)") (class "Default")
      (node (ref "C34") (pin "2") (pinfunction "2_2") (pintype "passive"))
      (node (ref "IC8") (pin "6") (pinfunction "V-_6") (pintype "power_in"))
    )
    (net (code "116") (name "Net-(IC10-C1+)") (class "Default")
      (node (ref "C54") (pin "2") (pinfunction "2_2") (pintype "passive"))
      (node (ref "IC10") (pin "1") (pinfunction "C1+_1") (pintype "passive"))
    )
    (net (code "117") (name "Net-(IC10-C1-)") (class "Default")
      (node (ref "C54") (pin "1") (pinfunction "1_1") (pintype "passive"))
      (node (ref "IC10") (pin "3") (pinfunction "C1-_3") (pintype "passive"))
    )
    (net (code "118") (name "Net-(IC10-C2+)") (class "Default")
      (node (ref "C55") (pin "2") (pinfunction "2_2") (pintype "passive"))
      (node (ref "IC10") (pin "4") (pinfunction "C2+_4") (pintype "passive"))
    )
    (net (code "119") (name "Net-(IC10-C2-)") (class "Default")
      (node (ref "C55") (pin "1") (pinfunction "1_1") (pintype "passive"))
      (node (ref "IC10") (pin "5") (pinfunction "C2-_5") (pintype "passive"))
    )
    (net (code "120") (name "Net-(IC10-V+)") (class "Default")
      (node (ref "C56") (pin "2") (pinfunction "2_2") (pintype "passive"))
      (node (ref "IC10") (pin "2") (pinfunction "V+_2") (pintype "power_in"))
    )
    (net (code "121") (name "Net-(IC10-V-)") (class "Default")
      (node (ref "C57") (pin "2") (pinfunction "2_2") (pintype "passive"))
      (node (ref "IC10") (pin "6") (pinfunction "V-_6") (pintype "power_in"))
    )
    (net (code "122") (name "Net-(IC11-C1+)") (class "Default")
      (node (ref "C67") (pin "2") (pinfunction "2_2") (pintype "passive"))
      (node (ref "IC11") (pin "1") (pinfunction "C1+_1") (pintype "passive"))
    )
    (net (code "123") (name "Net-(IC11-C1-)") (class "Default")
      (node (ref "C67") (pin "1") (pinfunction "1_1") (pintype "passive"))
      (node (ref "IC11") (pin "3") (pinfunction "C1-_3") (pintype "passive"))
    )
    (net (code "124") (name "Net-(IC11-C2+)") (class "Default")
      (node (ref "C68") (pin "2") (pinfunction "2_2") (pintype "passive"))
      (node (ref "IC11") (pin "4") (pinfunction "C2+_4") (pintype "passive"))
    )
    (net (code "125") (name "Net-(IC11-C2-)") (class "Default")
      (node (ref "C68") (pin "1") (pinfunction "1_1") (pintype "passive"))
      (node (ref "IC11") (pin "5") (pinfunction "C2-_5") (pintype "passive"))
    )
    (net (code "126") (name "Net-(IC11-V+)") (class "Default")
      (node (ref "C69") (pin "2") (pinfunction "2_2") (pintype "passive"))
      (node (ref "IC11") (pin "2") (pinfunction "V+_2") (pintype "power_in"))
    )
    (net (code "127") (name "Net-(IC11-V-)") (class "Default")
      (node (ref "C70") (pin "2") (pinfunction "2_2") (pintype "passive"))
      (node (ref "IC11") (pin "6") (pinfunction "V-_6") (pintype "power_in"))
    )
    (net (code "128") (name "Net-(IC12-C1+)") (class "Default")
      (node (ref "C72") (pin "2") (pinfunction "2_2") (pintype "passive"))
      (node (ref "IC12") (pin "1") (pinfunction "C1+_1") (pintype "passive"))
    )
    (net (code "129") (name "Net-(IC12-C1-)") (class "Default")
      (node (ref "C72") (pin "1") (pinfunction "1_1") (pintype "passive"))
      (node (ref "IC12") (pin "3") (pinfunction "C1-_3") (pintype "passive"))
    )
    (net (code "130") (name "Net-(IC12-C2+)") (class "Default")
      (node (ref "C73") (pin "2") (pinfunction "2_2") (pintype "passive"))
      (node (ref "IC12") (pin "4") (pinfunction "C2+_4") (pintype "passive"))
    )
    (net (code "131") (name "Net-(IC12-C2-)") (class "Default")
      (node (ref "C73") (pin "1") (pinfunction "1_1") (pintype "passive"))
      (node (ref "IC12") (pin "5") (pinfunction "C2-_5") (pintype "passive"))
    )
    (net (code "132") (name "Net-(IC12-V+)") (class "Default")
      (node (ref "C74") (pin "2") (pinfunction "2_2") (pintype "passive"))
      (node (ref "IC12") (pin "2") (pinfunction "V+_2") (pintype "power_in"))
    )
    (net (code "133") (name "Net-(IC12-V-)") (class "Default")
      (node (ref "C75") (pin "2") (pinfunction "2_2") (pintype "passive"))
      (node (ref "IC12") (pin "6") (pinfunction "V-_6") (pintype "power_in"))
    )
    (net (code "134") (name "Net-(IC13-C1+)") (class "Default")
      (node (ref "C77") (pin "2") (pinfunction "2_2") (pintype "passive"))
      (node (ref "IC13") (pin "1") (pinfunction "C1+_1") (pintype "passive"))
    )
    (net (code "135") (name "Net-(IC13-C1-)") (class "Default")
      (node (ref "C77") (pin "1") (pinfunction "1_1") (pintype "passive"))
      (node (ref "IC13") (pin "3") (pinfunction "C1-_3") (pintype "passive"))
    )
    (net (code "136") (name "Net-(IC13-C2+)") (class "Default")
      (node (ref "C78") (pin "2") (pinfunction "2_2") (pintype "passive"))
      (node (ref "IC13") (pin "4") (pinfunction "C2+_4") (pintype "passive"))
    )
    (net (code "137") (name "Net-(IC13-C2-)") (class "Default")
      (node (ref "C78") (pin "1") (pinfunction "1_1") (pintype "passive"))
      (node (ref "IC13") (pin "5") (pinfunction "C2-_5") (pintype "passive"))
    )
    (net (code "138") (name "Net-(IC13-V+)") (class "Default")
      (node (ref "C79") (pin "2") (pinfunction "2_2") (pintype "passive"))
      (node (ref "IC13") (pin "2") (pinfunction "V+_2") (pintype "power_in"))
    )
    (net (code "139") (name "Net-(IC13-V-)") (class "Default")
      (node (ref "C80") (pin "2") (pinfunction "2_2") (pintype "passive"))
      (node (ref "IC13") (pin "6") (pinfunction "V-_6") (pintype "power_in"))
    )
    (net (code "140") (name "Net-(IC15-C1+)") (class "Default")
      (node (ref "C89") (pin "2") (pinfunction "2_2") (pintype "passive"))
      (node (ref "IC15") (pin "1") (pinfunction "C1+_1") (pintype "passive"))
    )
    (net (code "141") (name "Net-(IC15-C1-)") (class "Default")
      (node (ref "C89") (pin "1") (pinfunction "1_1") (pintype "passive"))
      (node (ref "IC15") (pin "3") (pinfunction "C1-_3") (pintype "passive"))
    )
    (net (code "142") (name "Net-(IC15-C2+)") (class "Default")
      (node (ref "C90") (pin "2") (pinfunction "2_2") (pintype "passive"))
      (node (ref "IC15") (pin "4") (pinfunction "C2+_4") (pintype "passive"))
    )
    (net (code "143") (name "Net-(IC15-C2-)") (class "Default")
      (node (ref "C90") (pin "1") (pinfunction "1_1") (pintype "passive"))
      (node (ref "IC15") (pin "5") (pinfunction "C2-_5") (pintype "passive"))
    )
    (net (code "144") (name "Net-(IC15-V+)") (class "Default")
      (node (ref "C91") (pin "2") (pinfunction "2_2") (pintype "passive"))
      (node (ref "IC15") (pin "2") (pinfunction "V+_2") (pintype "power_in"))
    )
    (net (code "145") (name "Net-(IC15-V-)") (class "Default")
      (node (ref "C92") (pin "2") (pinfunction "2_2") (pintype "passive"))
      (node (ref "IC15") (pin "6") (pinfunction "V-_6") (pintype "power_in"))
    )
    (net (code "146") (name "Net-(IC16-C1+)") (class "Default")
      (node (ref "C102") (pin "2") (pinfunction "2_2") (pintype "passive"))
      (node (ref "IC16") (pin "1") (pinfunction "C1+_1") (pintype "passive"))
    )
    (net (code "147") (name "Net-(IC16-C1-)") (class "Default")
      (node (ref "C102") (pin "1") (pinfunction "1_1") (pintype "passive"))
      (node (ref "IC16") (pin "3") (pinfunction "C1-_3") (pintype "passive"))
    )
    (net (code "148") (name "Net-(IC16-C2+)") (class "Default")
      (node (ref "C103") (pin "2") (pinfunction "2_2") (pintype "passive"))
      (node (ref "IC16") (pin "4") (pinfunction "C2+_4") (pintype "passive"))
    )
    (net (code "149") (name "Net-(IC16-C2-)") (class "Default")
      (node (ref "C103") (pin "1") (pinfunction "1_1") (pintype "passive"))
      (node (ref "IC16") (pin "5") (pinfunction "C2-_5") (pintype "passive"))
    )
    (net (code "150") (name "Net-(IC16-V+)") (class "Default")
      (node (ref "C104") (pin "2") (pinfunction "2_2") (pintype "passive"))
      (node (ref "IC16") (pin "2") (pinfunction "V+_2") (pintype "power_in"))
    )
    (net (code "151") (name "Net-(IC16-V-)") (class "Default")
      (node (ref "C105") (pin "2") (pinfunction "2_2") (pintype "passive"))
      (node (ref "IC16") (pin "6") (pinfunction "V-_6") (pintype "power_in"))
    )
    (net (code "152") (name "Net-(IC17-C1+)") (class "Default")
      (node (ref "C107") (pin "2") (pinfunction "2_2") (pintype "passive"))
      (node (ref "IC17") (pin "1") (pinfunction "C1+_1") (pintype "passive"))
    )
    (net (code "153") (name "Net-(IC17-C1-)") (class "Default")
      (node (ref "C107") (pin "1") (pinfunction "1_1") (pintype "passive"))
      (node (ref "IC17") (pin "3") (pinfunction "C1-_3") (pintype "passive"))
    )
    (net (code "154") (name "Net-(IC17-C2+)") (class "Default")
      (node (ref "C108") (pin "2") (pinfunction "2_2") (pintype "passive"))
      (node (ref "IC17") (pin "4") (pinfunction "C2+_4") (pintype "passive"))
    )
    (net (code "155") (name "Net-(IC17-C2-)") (class "Default")
      (node (ref "C108") (pin "1") (pinfunction "1_1") (pintype "passive"))
      (node (ref "IC17") (pin "5") (pinfunction "C2-_5") (pintype "passive"))
    )
    (net (code "156") (name "Net-(IC17-V+)") (class "Default")
      (node (ref "C109") (pin "2") (pinfunction "2_2") (pintype "passive"))
      (node (ref "IC17") (pin "2") (pinfunction "V+_2") (pintype "power_in"))
    )
    (net (code "157") (name "Net-(IC17-V-)") (class "Default")
      (node (ref "C110") (pin "2") (pinfunction "2_2") (pintype "passive"))
      (node (ref "IC17") (pin "6") (pinfunction "V-_6") (pintype "power_in"))
    )
    (net (code "158") (name "Net-(IC18-C1+)") (class "Default")
      (node (ref "C112") (pin "2") (pinfunction "2_2") (pintype "passive"))
      (node (ref "IC18") (pin "1") (pinfunction "C1+_1") (pintype "passive"))
    )
    (net (code "159") (name "Net-(IC18-C1-)") (class "Default")
      (node (ref "C112") (pin "1") (pinfunction "1_1") (pintype "passive"))
      (node (ref "IC18") (pin "3") (pinfunction "C1-_3") (pintype "passive"))
    )
    (net (code "160") (name "Net-(IC18-C2+)") (class "Default")
      (node (ref "C113") (pin "2") (pinfunction "2_2") (pintype "passive"))
      (node (ref "IC18") (pin "4") (pinfunction "C2+_4") (pintype "passive"))
    )
    (net (code "161") (name "Net-(IC18-C2-)") (class "Default")
      (node (ref "C113") (pin "1") (pinfunction "1_1") (pintype "passive"))
      (node (ref "IC18") (pin "5") (pinfunction "C2-_5") (pintype "passive"))
    )
    (net (code "162") (name "Net-(IC18-V+)") (class "Default")
      (node (ref "C114") (pin "2") (pinfunction "2_2") (pintype "passive"))
      (node (ref "IC18") (pin "2") (pinfunction "V+_2") (pintype "power_in"))
    )
    (net (code "163") (name "Net-(IC18-V-)") (class "Default")
      (node (ref "C115") (pin "2") (pinfunction "2_2") (pintype "passive"))
      (node (ref "IC18") (pin "6") (pinfunction "V-_6") (pintype "power_in"))
    )
    (net (code "164") (name "Net-(RN2A-2)") (class "Default")
      (node (ref "DAISY_IN") (pin "2") (pinfunction "2_2") (pintype "passive"))
      (node (ref "RN2") (pin "A2") (pinfunction "2_A2") (pintype "passive"))
    )
    (net (code "165") (name "Net-(RN2B-2)") (class "Default")
      (node (ref "DAISY_IN") (pin "3") (pinfunction "3_3") (pintype "passive"))
      (node (ref "RN2") (pin "B2") (pinfunction "2_B2") (pintype "passive"))
    )
    (net (code "166") (name "RTS1E") (class "Default")
      (node (ref "IC5") (pin "7") (pinfunction "DOUT2_7") (pintype "output"))
      (node (ref "U$1") (pin "P4.1") (pinfunction "1_P4.1") (pintype "passive"))
    )
    (net (code "167") (name "RTS1E1") (class "Default")
      (node (ref "IC10") (pin "7") (pinfunction "DOUT2_7") (pintype "output"))
      (node (ref "U$1") (pin "P8.1") (pinfunction "1_P8.1") (pintype "passive"))
    )
    (net (code "168") (name "RTS1E2") (class "Default")
      (node (ref "IC15") (pin "7") (pinfunction "DOUT2_7") (pintype "output"))
      (node (ref "U$1") (pin "P12.1") (pinfunction "1_P12.1") (pintype "passive"))
      (node (ref "X1") (pin "1") (pinfunction "8_1") (pintype "passive"))
    )
    (net (code "169") (name "RTS1I") (class "Default")
      (node (ref "FTDI1") (pin "18") (pinfunction "DB2/RTS_18") (pintype "bidirectional"))
      (node (ref "IC5") (pin "10") (pinfunction "DIN2_10") (pintype "input"))
    )
    (net (code "170") (name "RTS1I1") (class "Default")
      (node (ref "FTDI2") (pin "18") (pinfunction "DB2/RTS_18") (pintype "bidirectional"))
      (node (ref "IC10") (pin "10") (pinfunction "DIN2_10") (pintype "input"))
    )
    (net (code "171") (name "RTS1I2") (class "Default")
      (node (ref "FTDI3") (pin "18") (pinfunction "DB2/RTS_18") (pintype "bidirectional"))
      (node (ref "IC15") (pin "10") (pinfunction "DIN2_10") (pintype "input"))
    )
    (net (code "172") (name "RTS2E") (class "Default")
      (node (ref "IC6") (pin "7") (pinfunction "DOUT2_7") (pintype "output"))
      (node (ref "U$1") (pin "P3.1") (pinfunction "1_P3.1") (pintype "passive"))
    )
    (net (code "173") (name "RTS2E1") (class "Default")
      (node (ref "IC11") (pin "7") (pinfunction "DOUT2_7") (pintype "output"))
      (node (ref "U$1") (pin "P7.1") (pinfunction "1_P7.1") (pintype "passive"))
    )
    (net (code "174") (name "RTS2E2") (class "Default")
      (node (ref "IC16") (pin "7") (pinfunction "DOUT2_7") (pintype "output"))
      (node (ref "U$1") (pin "P11.1") (pinfunction "1_P11.1") (pintype "passive"))
    )
    (net (code "175") (name "RTS2I") (class "Default")
      (node (ref "FTDI1") (pin "28") (pinfunction "DB2/RTS_28") (pintype "bidirectional"))
      (node (ref "IC6") (pin "10") (pinfunction "DIN2_10") (pintype "input"))
    )
    (net (code "176") (name "RTS2I1") (class "Default")
      (node (ref "FTDI2") (pin "28") (pinfunction "DB2/RTS_28") (pintype "bidirectional"))
      (node (ref "IC11") (pin "10") (pinfunction "DIN2_10") (pintype "input"))
    )
    (net (code "177") (name "RTS2I2") (class "Default")
      (node (ref "FTDI3") (pin "28") (pinfunction "DB2/RTS_28") (pintype "bidirectional"))
      (node (ref "IC16") (pin "10") (pinfunction "DIN2_10") (pintype "input"))
    )
    (net (code "178") (name "RTS3E") (class "Default")
      (node (ref "IC7") (pin "7") (pinfunction "DOUT2_7") (pintype "output"))
      (node (ref "U$1") (pin "P2.1") (pinfunction "1_P2.1") (pintype "passive"))
    )
    (net (code "179") (name "RTS3E1") (class "Default")
      (node (ref "IC12") (pin "7") (pinfunction "DOUT2_7") (pintype "output"))
      (node (ref "U$1") (pin "P6.1") (pinfunction "1_P6.1") (pintype "passive"))
    )
    (net (code "180") (name "RTS3E2") (class "Default")
      (node (ref "IC17") (pin "7") (pinfunction "DOUT2_7") (pintype "output"))
      (node (ref "U$1") (pin "P10.1") (pinfunction "1_P10.1") (pintype "passive"))
    )
    (net (code "181") (name "RTS3I") (class "Default")
      (node (ref "FTDI1") (pin "40") (pinfunction "DB2/RTS_40") (pintype "bidirectional"))
      (node (ref "IC7") (pin "10") (pinfunction "DIN2_10") (pintype "input"))
    )
    (net (code "182") (name "RTS3I1") (class "Default")
      (node (ref "FTDI2") (pin "40") (pinfunction "DB2/RTS_40") (pintype "bidirectional"))
      (node (ref "IC12") (pin "10") (pinfunction "DIN2_10") (pintype "input"))
    )
    (net (code "183") (name "RTS3I2") (class "Default")
      (node (ref "FTDI3") (pin "40") (pinfunction "DB2/RTS_40") (pintype "bidirectional"))
      (node (ref "IC17") (pin "10") (pinfunction "DIN2_10") (pintype "input"))
    )
    (net (code "184") (name "RTS4E") (class "Default")
      (node (ref "IC8") (pin "7") (pinfunction "DOUT2_7") (pintype "output"))
      (node (ref "U$1") (pin "P1.1") (pinfunction "1_P1.1") (pintype "passive"))
    )
    (net (code "185") (name "RTS4E1") (class "Default")
      (node (ref "IC13") (pin "7") (pinfunction "DOUT2_7") (pintype "output"))
      (node (ref "U$1") (pin "P5.1") (pinfunction "1_P5.1") (pintype "passive"))
    )
    (net (code "186") (name "RTS4E2") (class "Default")
      (node (ref "IC18") (pin "7") (pinfunction "DOUT2_7") (pintype "output"))
      (node (ref "U$1") (pin "P9.1") (pinfunction "1_P9.1") (pintype "passive"))
    )
    (net (code "187") (name "RTS4I") (class "Default")
      (node (ref "FTDI1") (pin "53") (pinfunction "DB2/RTS_53") (pintype "bidirectional"))
      (node (ref "IC8") (pin "10") (pinfunction "DIN2_10") (pintype "input"))
    )
    (net (code "188") (name "RTS4I1") (class "Default")
      (node (ref "FTDI2") (pin "53") (pinfunction "DB2/RTS_53") (pintype "bidirectional"))
      (node (ref "IC13") (pin "10") (pinfunction "DIN2_10") (pintype "input"))
    )
    (net (code "189") (name "RTS4I2") (class "Default")
      (node (ref "FTDI3") (pin "53") (pinfunction "DB2/RTS_53") (pintype "bidirectional"))
      (node (ref "IC18") (pin "10") (pinfunction "DIN2_10") (pintype "input"))
    )
    (net (code "190") (name "RXD1E") (class "Default")
      (node (ref "IC5") (pin "13") (pinfunction "RIN1_13") (pintype "input"))
      (node (ref "U$1") (pin "P4.6") (pinfunction "6_P4.6") (pintype "passive"))
    )
    (net (code "191") (name "RXD1E1") (class "Default")
      (node (ref "IC10") (pin "13") (pinfunction "RIN1_13") (pintype "input"))
      (node (ref "U$1") (pin "P8.6") (pinfunction "6_P8.6") (pintype "passive"))
    )
    (net (code "192") (name "RXD1E2") (class "Default")
      (node (ref "IC15") (pin "13") (pinfunction "RIN1_13") (pintype "input"))
      (node (ref "U$1") (pin "P12.6") (pinfunction "6_P12.6") (pintype "passive"))
      (node (ref "X1") (pin "6") (pinfunction "3_6") (pintype "passive"))
    )
    (net (code "193") (name "RXD1I") (class "Default")
      (node (ref "FTDI1") (pin "17") (pinfunction "DB1/RXD_17") (pintype "bidirectional"))
      (node (ref "IC5") (pin "12") (pinfunction "ROUT1_12") (pintype "output"))
    )
    (net (code "194") (name "RXD1I1") (class "Default")
      (node (ref "FTDI2") (pin "17") (pinfunction "DB1/RXD_17") (pintype "bidirectional"))
      (node (ref "IC10") (pin "12") (pinfunction "ROUT1_12") (pintype "output"))
    )
    (net (code "195") (name "RXD1I2") (class "Default")
      (node (ref "FTDI3") (pin "17") (pinfunction "DB1/RXD_17") (pintype "bidirectional"))
      (node (ref "IC15") (pin "12") (pinfunction "ROUT1_12") (pintype "output"))
    )
    (net (code "196") (name "RXD2E") (class "Default")
      (node (ref "IC6") (pin "13") (pinfunction "RIN1_13") (pintype "input"))
      (node (ref "U$1") (pin "P3.6") (pinfunction "6_P3.6") (pintype "passive"))
    )
    (net (code "197") (name "RXD2E1") (class "Default")
      (node (ref "IC11") (pin "13") (pinfunction "RIN1_13") (pintype "input"))
      (node (ref "U$1") (pin "P7.6") (pinfunction "6_P7.6") (pintype "passive"))
    )
    (net (code "198") (name "RXD2E2") (class "Default")
      (node (ref "IC16") (pin "13") (pinfunction "RIN1_13") (pintype "input"))
      (node (ref "U$1") (pin "P11.6") (pinfunction "6_P11.6") (pintype "passive"))
    )
    (net (code "199") (name "RXD2I") (class "Default")
      (node (ref "FTDI1") (pin "27") (pinfunction "DB1/RXD_27") (pintype "bidirectional"))
      (node (ref "IC6") (pin "12") (pinfunction "ROUT1_12") (pintype "output"))
    )
    (net (code "200") (name "RXD2I1") (class "Default")
      (node (ref "FTDI2") (pin "27") (pinfunction "DB1/RXD_27") (pintype "bidirectional"))
      (node (ref "IC11") (pin "12") (pinfunction "ROUT1_12") (pintype "output"))
    )
    (net (code "201") (name "RXD2I2") (class "Default")
      (node (ref "FTDI3") (pin "27") (pinfunction "DB1/RXD_27") (pintype "bidirectional"))
      (node (ref "IC16") (pin "12") (pinfunction "ROUT1_12") (pintype "output"))
    )
    (net (code "202") (name "RXD3E") (class "Default")
      (node (ref "IC7") (pin "13") (pinfunction "RIN1_13") (pintype "input"))
      (node (ref "U$1") (pin "P2.6") (pinfunction "6_P2.6") (pintype "passive"))
    )
    (net (code "203") (name "RXD3E1") (class "Default")
      (node (ref "IC12") (pin "13") (pinfunction "RIN1_13") (pintype "input"))
      (node (ref "U$1") (pin "P6.6") (pinfunction "6_P6.6") (pintype "passive"))
    )
    (net (code "204") (name "RXD3E2") (class "Default")
      (node (ref "IC17") (pin "13") (pinfunction "RIN1_13") (pintype "input"))
      (node (ref "U$1") (pin "P10.6") (pinfunction "6_P10.6") (pintype "passive"))
    )
    (net (code "205") (name "RXD3I") (class "Default")
      (node (ref "FTDI1") (pin "39") (pinfunction "DB1/RXD_39") (pintype "bidirectional"))
      (node (ref "IC7") (pin "12") (pinfunction "ROUT1_12") (pintype "output"))
    )
    (net (code "206") (name "RXD3I1") (class "Default")
      (node (ref "FTDI2") (pin "39") (pinfunction "DB1/RXD_39") (pintype "bidirectional"))
      (node (ref "IC12") (pin "12") (pinfunction "ROUT1_12") (pintype "output"))
    )
    (net (code "207") (name "RXD3I2") (class "Default")
      (node (ref "FTDI3") (pin "39") (pinfunction "DB1/RXD_39") (pintype "bidirectional"))
      (node (ref "IC17") (pin "12") (pinfunction "ROUT1_12") (pintype "output"))
    )
    (net (code "208") (name "RXD4E") (class "Default")
      (node (ref "IC8") (pin "13") (pinfunction "RIN1_13") (pintype "input"))
      (node (ref "U$1") (pin "P1.6") (pinfunction "6_P1.6") (pintype "passive"))
    )
    (net (code "209") (name "RXD4E1") (class "Default")
      (node (ref "IC13") (pin "13") (pinfunction "RIN1_13") (pintype "input"))
      (node (ref "U$1") (pin "P5.6") (pinfunction "6_P5.6") (pintype "passive"))
    )
    (net (code "210") (name "RXD4E2") (class "Default")
      (node (ref "IC18") (pin "13") (pinfunction "RIN1_13") (pintype "input"))
      (node (ref "U$1") (pin "P9.6") (pinfunction "6_P9.6") (pintype "passive"))
    )
    (net (code "211") (name "RXD4I") (class "Default")
      (node (ref "FTDI1") (pin "52") (pinfunction "DB1/RXD_52") (pintype "bidirectional"))
      (node (ref "IC8") (pin "12") (pinfunction "ROUT1_12") (pintype "output"))
    )
    (net (code "212") (name "RXD4I1") (class "Default")
      (node (ref "FTDI2") (pin "52") (pinfunction "DB1/RXD_52") (pintype "bidirectional"))
      (node (ref "IC13") (pin "12") (pinfunction "ROUT1_12") (pintype "output"))
    )
    (net (code "213") (name "RXD4I2") (class "Default")
      (node (ref "FTDI3") (pin "52") (pinfunction "DB1/RXD_52") (pintype "bidirectional"))
      (node (ref "IC18") (pin "12") (pinfunction "ROUT1_12") (pintype "output"))
    )
    (net (code "214") (name "TXD1E") (class "Default")
      (node (ref "IC5") (pin "14") (pinfunction "DOUT1_14") (pintype "output"))
      (node (ref "U$1") (pin "P4.3") (pinfunction "3_P4.3") (pintype "passive"))
    )
    (net (code "215") (name "TXD1E1") (class "Default")
      (node (ref "IC10") (pin "14") (pinfunction "DOUT1_14") (pintype "output"))
      (node (ref "U$1") (pin "P8.3") (pinfunction "3_P8.3") (pintype "passive"))
    )
    (net (code "216") (name "TXD1E2") (class "Default")
      (node (ref "IC15") (pin "14") (pinfunction "DOUT1_14") (pintype "output"))
      (node (ref "U$1") (pin "P12.3") (pinfunction "3_P12.3") (pintype "passive"))
      (node (ref "X1") (pin "3") (pinfunction "6_3") (pintype "passive"))
    )
    (net (code "217") (name "TXD1I") (class "Default")
      (node (ref "FTDI1") (pin "16") (pinfunction "DB0/TXD_16") (pintype "bidirectional"))
      (node (ref "IC5") (pin "11") (pinfunction "DIN1_11") (pintype "input"))
    )
    (net (code "218") (name "TXD1I1") (class "Default")
      (node (ref "FTDI2") (pin "16") (pinfunction "DB0/TXD_16") (pintype "bidirectional"))
      (node (ref "IC10") (pin "11") (pinfunction "DIN1_11") (pintype "input"))
    )
    (net (code "219") (name "TXD1I2") (class "Default")
      (node (ref "FTDI3") (pin "16") (pinfunction "DB0/TXD_16") (pintype "bidirectional"))
      (node (ref "IC15") (pin "11") (pinfunction "DIN1_11") (pintype "input"))
    )
    (net (code "220") (name "TXD2E") (class "Default")
      (node (ref "IC6") (pin "14") (pinfunction "DOUT1_14") (pintype "output"))
      (node (ref "U$1") (pin "P3.3") (pinfunction "3_P3.3") (pintype "passive"))
    )
    (net (code "221") (name "TXD2E1") (class "Default")
      (node (ref "IC11") (pin "14") (pinfunction "DOUT1_14") (pintype "output"))
      (node (ref "U$1") (pin "P7.3") (pinfunction "3_P7.3") (pintype "passive"))
    )
    (net (code "222") (name "TXD2E2") (class "Default")
      (node (ref "IC16") (pin "14") (pinfunction "DOUT1_14") (pintype "output"))
      (node (ref "U$1") (pin "P11.3") (pinfunction "3_P11.3") (pintype "passive"))
    )
    (net (code "223") (name "TXD2I") (class "Default")
      (node (ref "FTDI1") (pin "26") (pinfunction "DB0/TXD_26") (pintype "bidirectional"))
      (node (ref "IC6") (pin "11") (pinfunction "DIN1_11") (pintype "input"))
    )
    (net (code "224") (name "TXD2I1") (class "Default")
      (node (ref "FTDI2") (pin "26") (pinfunction "DB0/TXD_26") (pintype "bidirectional"))
      (node (ref "IC11") (pin "11") (pinfunction "DIN1_11") (pintype "input"))
    )
    (net (code "225") (name "TXD2I2") (class "Default")
      (node (ref "FTDI3") (pin "26") (pinfunction "DB0/TXD_26") (pintype "bidirectional"))
      (node (ref "IC16") (pin "11") (pinfunction "DIN1_11") (pintype "input"))
    )
    (net (code "226") (name "TXD3E") (class "Default")
      (node (ref "IC7") (pin "14") (pinfunction "DOUT1_14") (pintype "output"))
      (node (ref "U$1") (pin "P2.3") (pinfunction "3_P2.3") (pintype "passive"))
    )
    (net (code "227") (name "TXD3E1") (class "Default")
      (node (ref "IC12") (pin "14") (pinfunction "DOUT1_14") (pintype "output"))
      (node (ref "U$1") (pin "P6.3") (pinfunction "3_P6.3") (pintype "passive"))
    )
    (net (code "228") (name "TXD3E2") (class "Default")
      (node (ref "IC17") (pin "14") (pinfunction "DOUT1_14") (pintype "output"))
      (node (ref "U$1") (pin "P10.3") (pinfunction "3_P10.3") (pintype "passive"))
    )
    (net (code "229") (name "TXD3I") (class "Default")
      (node (ref "FTDI1") (pin "38") (pinfunction "DB0/TXD_38") (pintype "bidirectional"))
      (node (ref "IC7") (pin "11") (pinfunction "DIN1_11") (pintype "input"))
    )
    (net (code "230") (name "TXD3I1") (class "Default")
      (node (ref "FTDI2") (pin "38") (pinfunction "DB0/TXD_38") (pintype "bidirectional"))
      (node (ref "IC12") (pin "11") (pinfunction "DIN1_11") (pintype "input"))
    )
    (net (code "231") (name "TXD3I2") (class "Default")
      (node (ref "FTDI3") (pin "38") (pinfunction "DB0/TXD_38") (pintype "bidirectional"))
      (node (ref "IC17") (pin "11") (pinfunction "DIN1_11") (pintype "input"))
    )
    (net (code "232") (name "TXD4E") (class "Default")
      (node (ref "IC8") (pin "14") (pinfunction "DOUT1_14") (pintype "output"))
      (node (ref "U$1") (pin "P1.3") (pinfunction "3_P1.3") (pintype "passive"))
    )
    (net (code "233") (name "TXD4E1") (class "Default")
      (node (ref "IC13") (pin "14") (pinfunction "DOUT1_14") (pintype "output"))
      (node (ref "U$1") (pin "P5.3") (pinfunction "3_P5.3") (pintype "passive"))
    )
    (net (code "234") (name "TXD4E2") (class "Default")
      (node (ref "IC18") (pin "14") (pinfunction "DOUT1_14") (pintype "output"))
      (node (ref "U$1") (pin "P9.3") (pinfunction "3_P9.3") (pintype "passive"))
    )
    (net (code "235") (name "TXD4I") (class "Default")
      (node (ref "FTDI1") (pin "48") (pinfunction "DB0/TXD_48") (pintype "bidirectional"))
      (node (ref "IC8") (pin "11") (pinfunction "DIN1_11") (pintype "input"))
    )
    (net (code "236") (name "TXD4I1") (class "Default")
      (node (ref "FTDI2") (pin "48") (pinfunction "DB0/TXD_48") (pintype "bidirectional"))
      (node (ref "IC13") (pin "11") (pinfunction "DIN1_11") (pintype "input"))
    )
    (net (code "237") (name "TXD4I2") (class "Default")
      (node (ref "FTDI3") (pin "48") (pinfunction "DB0/TXD_48") (pintype "bidirectional"))
      (node (ref "IC18") (pin "11") (pinfunction "DIN1_11") (pintype "input"))
    )
    (net (code "238") (name "unconnected-(FTDI1A-DB4{slash}DTR-Pad21)") (class "Default")
      (node (ref "FTDI1") (pin "21") (pinfunction "DB4/DTR_21") (pintype "bidirectional"))
    )
    (net (code "239") (name "unconnected-(FTDI1A-DB5{slash}DSR-Pad22)") (class "Default")
      (node (ref "FTDI1") (pin "22") (pinfunction "DB5/DSR_22") (pintype "bidirectional"))
    )
    (net (code "240") (name "unconnected-(FTDI1A-DB6{slash}DCD-Pad23)") (class "Default")
      (node (ref "FTDI1") (pin "23") (pinfunction "DB6/DCD_23") (pintype "bidirectional"))
    )
    (net (code "241") (name "unconnected-(FTDI1A-DB7{slash}RI-Pad24)") (class "Default")
      (node (ref "FTDI1") (pin "24") (pinfunction "DB7/RI_24") (pintype "bidirectional"))
    )
    (net (code "242") (name "unconnected-(FTDI1B-DB4{slash}DTR-Pad30)") (class "Default")
      (node (ref "FTDI1") (pin "30") (pinfunction "DB4/DTR_30") (pintype "bidirectional"))
    )
    (net (code "243") (name "unconnected-(FTDI1B-DB5{slash}DSR-Pad32)") (class "Default")
      (node (ref "FTDI1") (pin "32") (pinfunction "DB5/DSR_32") (pintype "bidirectional"))
    )
    (net (code "244") (name "unconnected-(FTDI1B-DB6{slash}DCD-Pad33)") (class "Default")
      (node (ref "FTDI1") (pin "33") (pinfunction "DB6/DCD_33") (pintype "bidirectional"))
    )
    (net (code "245") (name "unconnected-(FTDI1B-DB7{slash}RI-Pad34)") (class "Default")
      (node (ref "FTDI1") (pin "34") (pinfunction "DB7/RI_34") (pintype "bidirectional"))
    )
    (net (code "246") (name "unconnected-(FTDI1C-DB4{slash}DTR-Pad43)") (class "Default")
      (node (ref "FTDI1") (pin "43") (pinfunction "DB4/DTR_43") (pintype "bidirectional"))
    )
    (net (code "247") (name "unconnected-(FTDI1C-DB5{slash}DSR-Pad44)") (class "Default")
      (node (ref "FTDI1") (pin "44") (pinfunction "DB5/DSR_44") (pintype "bidirectional"))
    )
    (net (code "248") (name "unconnected-(FTDI1C-DB6{slash}DCD-Pad45)") (class "Default")
      (node (ref "FTDI1") (pin "45") (pinfunction "DB6/DCD_45") (pintype "bidirectional"))
    )
    (net (code "249") (name "unconnected-(FTDI1C-DB7{slash}RI-Pad46)") (class "Default")
      (node (ref "FTDI1") (pin "46") (pinfunction "DB7/RI_46") (pintype "bidirectional"))
    )
    (net (code "250") (name "unconnected-(FTDI1D-EECLK-Pad62)") (class "Default")
      (node (ref "FTDI1") (pin "62") (pinfunction "EECLK_62") (pintype "output"))
    )
    (net (code "251") (name "unconnected-(FTDI1D-EECS-Pad63)") (class "Default")
      (node (ref "FTDI1") (pin "63") (pinfunction "EECS_63") (pintype "bidirectional"))
    )
    (net (code "252") (name "unconnected-(FTDI1D-EEDATA-Pad61)") (class "Default")
      (node (ref "FTDI1") (pin "61") (pinfunction "EEDATA_61") (pintype "bidirectional"))
    )
    (net (code "253") (name "unconnected-(FTDI1D-PWREN#-Pad60)") (class "Default")
      (node (ref "FTDI1") (pin "60") (pinfunction "PWREN#_60") (pintype "output"))
    )
    (net (code "254") (name "unconnected-(FTDI1D-SUSPEND#-Pad36)") (class "Default")
      (node (ref "FTDI1") (pin "36") (pinfunction "SUSPEND#_36") (pintype "output"))
    )
    (net (code "255") (name "unconnected-(FTDI1D-XTOUT-Pad3)") (class "Default")
      (node (ref "FTDI1") (pin "3") (pinfunction "XTOUT_3") (pintype "output"))
    )
    (net (code "256") (name "unconnected-(FTDI1E-DB4{slash}DTR-Pad55)") (class "Default")
      (node (ref "FTDI1") (pin "55") (pinfunction "DB4/DTR_55") (pintype "bidirectional"))
    )
    (net (code "257") (name "unconnected-(FTDI1E-DB5{slash}DSR-Pad57)") (class "Default")
      (node (ref "FTDI1") (pin "57") (pinfunction "DB5/DSR_57") (pintype "bidirectional"))
    )
    (net (code "258") (name "unconnected-(FTDI1E-DB6{slash}DCD-Pad58)") (class "Default")
      (node (ref "FTDI1") (pin "58") (pinfunction "DB6/DCD_58") (pintype "bidirectional"))
    )
    (net (code "259") (name "unconnected-(FTDI1E-DB7{slash}RI-Pad59)") (class "Default")
      (node (ref "FTDI1") (pin "59") (pinfunction "DB7/RI_59") (pintype "bidirectional"))
    )
    (net (code "260") (name "unconnected-(FTDI2A-DB4{slash}DTR-Pad21)") (class "Default")
      (node (ref "FTDI2") (pin "21") (pinfunction "DB4/DTR_21") (pintype "bidirectional"))
    )
    (net (code "261") (name "unconnected-(FTDI2A-DB5{slash}DSR-Pad22)") (class "Default")
      (node (ref "FTDI2") (pin "22") (pinfunction "DB5/DSR_22") (pintype "bidirectional"))
    )
    (net (code "262") (name "unconnected-(FTDI2A-DB6{slash}DCD-Pad23)") (class "Default")
      (node (ref "FTDI2") (pin "23") (pinfunction "DB6/DCD_23") (pintype "bidirectional"))
    )
    (net (code "263") (name "unconnected-(FTDI2A-DB7{slash}RI-Pad24)") (class "Default")
      (node (ref "FTDI2") (pin "24") (pinfunction "DB7/RI_24") (pintype "bidirectional"))
    )
    (net (code "264") (name "unconnected-(FTDI2B-DB4{slash}DTR-Pad30)") (class "Default")
      (node (ref "FTDI2") (pin "30") (pinfunction "DB4/DTR_30") (pintype "bidirectional"))
    )
    (net (code "265") (name "unconnected-(FTDI2B-DB5{slash}DSR-Pad32)") (class "Default")
      (node (ref "FTDI2") (pin "32") (pinfunction "DB5/DSR_32") (pintype "bidirectional"))
    )
    (net (code "266") (name "unconnected-(FTDI2B-DB6{slash}DCD-Pad33)") (class "Default")
      (node (ref "FTDI2") (pin "33") (pinfunction "DB6/DCD_33") (pintype "bidirectional"))
    )
    (net (code "267") (name "unconnected-(FTDI2B-DB7{slash}RI-Pad34)") (class "Default")
      (node (ref "FTDI2") (pin "34") (pinfunction "DB7/RI_34") (pintype "bidirectional"))
    )
    (net (code "268") (name "unconnected-(FTDI2C-DB4{slash}DTR-Pad43)") (class "Default")
      (node (ref "FTDI2") (pin "43") (pinfunction "DB4/DTR_43") (pintype "bidirectional"))
    )
    (net (code "269") (name "unconnected-(FTDI2C-DB5{slash}DSR-Pad44)") (class "Default")
      (node (ref "FTDI2") (pin "44") (pinfunction "DB5/DSR_44") (pintype "bidirectional"))
    )
    (net (code "270") (name "unconnected-(FTDI2C-DB6{slash}DCD-Pad45)") (class "Default")
      (node (ref "FTDI2") (pin "45") (pinfunction "DB6/DCD_45") (pintype "bidirectional"))
    )
    (net (code "271") (name "unconnected-(FTDI2C-DB7{slash}RI-Pad46)") (class "Default")
      (node (ref "FTDI2") (pin "46") (pinfunction "DB7/RI_46") (pintype "bidirectional"))
    )
    (net (code "272") (name "unconnected-(FTDI2D-EECLK-Pad62)") (class "Default")
      (node (ref "FTDI2") (pin "62") (pinfunction "EECLK_62") (pintype "output"))
    )
    (net (code "273") (name "unconnected-(FTDI2D-EECS-Pad63)") (class "Default")
      (node (ref "FTDI2") (pin "63") (pinfunction "EECS_63") (pintype "bidirectional"))
    )
    (net (code "274") (name "unconnected-(FTDI2D-EEDATA-Pad61)") (class "Default")
      (node (ref "FTDI2") (pin "61") (pinfunction "EEDATA_61") (pintype "bidirectional"))
    )
    (net (code "275") (name "unconnected-(FTDI2D-PWREN#-Pad60)") (class "Default")
      (node (ref "FTDI2") (pin "60") (pinfunction "PWREN#_60") (pintype "output"))
    )
    (net (code "276") (name "unconnected-(FTDI2D-SUSPEND#-Pad36)") (class "Default")
      (node (ref "FTDI2") (pin "36") (pinfunction "SUSPEND#_36") (pintype "output"))
    )
    (net (code "277") (name "unconnected-(FTDI2D-XTOUT-Pad3)") (class "Default")
      (node (ref "FTDI2") (pin "3") (pinfunction "XTOUT_3") (pintype "output"))
    )
    (net (code "278") (name "unconnected-(FTDI2E-DB4{slash}DTR-Pad55)") (class "Default")
      (node (ref "FTDI2") (pin "55") (pinfunction "DB4/DTR_55") (pintype "bidirectional"))
    )
    (net (code "279") (name "unconnected-(FTDI2E-DB5{slash}DSR-Pad57)") (class "Default")
      (node (ref "FTDI2") (pin "57") (pinfunction "DB5/DSR_57") (pintype "bidirectional"))
    )
    (net (code "280") (name "unconnected-(FTDI2E-DB6{slash}DCD-Pad58)") (class "Default")
      (node (ref "FTDI2") (pin "58") (pinfunction "DB6/DCD_58") (pintype "bidirectional"))
    )
    (net (code "281") (name "unconnected-(FTDI2E-DB7{slash}RI-Pad59)") (class "Default")
      (node (ref "FTDI2") (pin "59") (pinfunction "DB7/RI_59") (pintype "bidirectional"))
    )
    (net (code "282") (name "unconnected-(FTDI3A-DB4{slash}DTR-Pad21)") (class "Default")
      (node (ref "FTDI3") (pin "21") (pinfunction "DB4/DTR_21") (pintype "bidirectional"))
    )
    (net (code "283") (name "unconnected-(FTDI3A-DB5{slash}DSR-Pad22)") (class "Default")
      (node (ref "FTDI3") (pin "22") (pinfunction "DB5/DSR_22") (pintype "bidirectional"))
    )
    (net (code "284") (name "unconnected-(FTDI3A-DB6{slash}DCD-Pad23)") (class "Default")
      (node (ref "FTDI3") (pin "23") (pinfunction "DB6/DCD_23") (pintype "bidirectional"))
    )
    (net (code "285") (name "unconnected-(FTDI3A-DB7{slash}RI-Pad24)") (class "Default")
      (node (ref "FTDI3") (pin "24") (pinfunction "DB7/RI_24") (pintype "bidirectional"))
    )
    (net (code "286") (name "unconnected-(FTDI3B-DB4{slash}DTR-Pad30)") (class "Default")
      (node (ref "FTDI3") (pin "30") (pinfunction "DB4/DTR_30") (pintype "bidirectional"))
    )
    (net (code "287") (name "unconnected-(FTDI3B-DB5{slash}DSR-Pad32)") (class "Default")
      (node (ref "FTDI3") (pin "32") (pinfunction "DB5/DSR_32") (pintype "bidirectional"))
    )
    (net (code "288") (name "unconnected-(FTDI3B-DB6{slash}DCD-Pad33)") (class "Default")
      (node (ref "FTDI3") (pin "33") (pinfunction "DB6/DCD_33") (pintype "bidirectional"))
    )
    (net (code "289") (name "unconnected-(FTDI3B-DB7{slash}RI-Pad34)") (class "Default")
      (node (ref "FTDI3") (pin "34") (pinfunction "DB7/RI_34") (pintype "bidirectional"))
    )
    (net (code "290") (name "unconnected-(FTDI3C-DB4{slash}DTR-Pad43)") (class "Default")
      (node (ref "FTDI3") (pin "43") (pinfunction "DB4/DTR_43") (pintype "bidirectional"))
    )
    (net (code "291") (name "unconnected-(FTDI3C-DB5{slash}DSR-Pad44)") (class "Default")
      (node (ref "FTDI3") (pin "44") (pinfunction "DB5/DSR_44") (pintype "bidirectional"))
    )
    (net (code "292") (name "unconnected-(FTDI3C-DB6{slash}DCD-Pad45)") (class "Default")
      (node (ref "FTDI3") (pin "45") (pinfunction "DB6/DCD_45") (pintype "bidirectional"))
    )
    (net (code "293") (name "unconnected-(FTDI3C-DB7{slash}RI-Pad46)") (class "Default")
      (node (ref "FTDI3") (pin "46") (pinfunction "DB7/RI_46") (pintype "bidirectional"))
    )
    (net (code "294") (name "unconnected-(FTDI3D-EECLK-Pad62)") (class "Default")
      (node (ref "FTDI3") (pin "62") (pinfunction "EECLK_62") (pintype "output"))
    )
    (net (code "295") (name "unconnected-(FTDI3D-EECS-Pad63)") (class "Default")
      (node (ref "FTDI3") (pin "63") (pinfunction "EECS_63") (pintype "bidirectional"))
    )
    (net (code "296") (name "unconnected-(FTDI3D-EEDATA-Pad61)") (class "Default")
      (node (ref "FTDI3") (pin "61") (pinfunction "EEDATA_61") (pintype "bidirectional"))
    )
    (net (code "297") (name "unconnected-(FTDI3D-PWREN#-Pad60)") (class "Default")
      (node (ref "FTDI3") (pin "60") (pinfunction "PWREN#_60") (pintype "output"))
    )
    (net (code "298") (name "unconnected-(FTDI3D-SUSPEND#-Pad36)") (class "Default")
      (node (ref "FTDI3") (pin "36") (pinfunction "SUSPEND#_36") (pintype "output"))
    )
    (net (code "299") (name "unconnected-(FTDI3D-XTOUT-Pad3)") (class "Default")
      (node (ref "FTDI3") (pin "3") (pinfunction "XTOUT_3") (pintype "output"))
    )
    (net (code "300") (name "unconnected-(FTDI3E-DB4{slash}DTR-Pad55)") (class "Default")
      (node (ref "FTDI3") (pin "55") (pinfunction "DB4/DTR_55") (pintype "bidirectional"))
    )
    (net (code "301") (name "unconnected-(FTDI3E-DB5{slash}DSR-Pad57)") (class "Default")
      (node (ref "FTDI3") (pin "57") (pinfunction "DB5/DSR_57") (pintype "bidirectional"))
    )
    (net (code "302") (name "unconnected-(FTDI3E-DB6{slash}DCD-Pad58)") (class "Default")
      (node (ref "FTDI3") (pin "58") (pinfunction "DB6/DCD_58") (pintype "bidirectional"))
    )
    (net (code "303") (name "unconnected-(FTDI3E-DB7{slash}RI-Pad59)") (class "Default")
      (node (ref "FTDI3") (pin "59") (pinfunction "DB7/RI_59") (pintype "bidirectional"))
    )
    (net (code "304") (name "unconnected-(HUB-EECLK-Pad5)") (class "Default")
      (node (ref "HUB") (pin "5") (pinfunction "EECLK_5") (pintype "output"))
    )
    (net (code "305") (name "unconnected-(HUB-EEDATA{slash}GANGED-Pad6)") (class "Default")
      (node (ref "HUB") (pin "6") (pinfunction "EEDATA/GANGED_6") (pintype "bidirectional"))
    )
    (net (code "306") (name "unconnected-(HUB-SUSPND-Pad32)") (class "Default")
      (node (ref "HUB") (pin "32") (pinfunction "SUSPND_32") (pintype "output"))
    )
    (net (code "307") (name "unconnected-(HUB-~{PWRON1}-Pad9)") (class "Default")
      (node (ref "HUB") (pin "9") (pinfunction "~{PWRON1}_9") (pintype "output"))
    )
    (net (code "308") (name "unconnected-(HUB-~{PWRON2}-Pad13)") (class "Default")
      (node (ref "HUB") (pin "13") (pinfunction "~{PWRON2}_13") (pintype "output"))
    )
    (net (code "309") (name "unconnected-(HUB-~{PWRON3}-Pad17)") (class "Default")
      (node (ref "HUB") (pin "17") (pinfunction "~{PWRON3}_17") (pintype "output"))
    )
    (net (code "310") (name "unconnected-(HUB-~{PWRON4}-Pad21)") (class "Default")
      (node (ref "HUB") (pin "21") (pinfunction "~{PWRON4}_21") (pintype "output"))
    )
    (net (code "311") (name "unconnected-(U$1A-2-PadP1.2)") (class "Default")
      (node (ref "U$1") (pin "P1.2") (pinfunction "2_P1.2") (pintype "passive"))
    )
    (net (code "312") (name "unconnected-(U$1A-7-PadP1.7)") (class "Default")
      (node (ref "U$1") (pin "P1.7") (pinfunction "7_P1.7") (pintype "passive"))
    )
    (net (code "313") (name "unconnected-(U$1B-2-PadP10.2)") (class "Default")
      (node (ref "U$1") (pin "P10.2") (pinfunction "2_P10.2") (pintype "passive"))
    )
    (net (code "314") (name "unconnected-(U$1B-7-PadP10.7)") (class "Default")
      (node (ref "U$1") (pin "P10.7") (pinfunction "7_P10.7") (pintype "passive"))
    )
    (net (code "315") (name "unconnected-(U$1C-2-PadP11.2)") (class "Default")
      (node (ref "U$1") (pin "P11.2") (pinfunction "2_P11.2") (pintype "passive"))
    )
    (net (code "316") (name "unconnected-(U$1C-7-PadP11.7)") (class "Default")
      (node (ref "U$1") (pin "P11.7") (pinfunction "7_P11.7") (pintype "passive"))
    )
    (net (code "317") (name "unconnected-(U$1D-7-PadP12.7)") (class "Default")
      (node (ref "U$1") (pin "P12.7") (pinfunction "7_P12.7") (pintype "passive"))
    )
    (net (code "318") (name "unconnected-(U$1F-2-PadP2.2)") (class "Default")
      (node (ref "U$1") (pin "P2.2") (pinfunction "2_P2.2") (pintype "passive"))
    )
    (net (code "319") (name "unconnected-(U$1F-7-PadP2.7)") (class "Default")
      (node (ref "U$1") (pin "P2.7") (pinfunction "7_P2.7") (pintype "passive"))
    )
    (net (code "320") (name "unconnected-(U$1G-2-PadP3.2)") (class "Default")
      (node (ref "U$1") (pin "P3.2") (pinfunction "2_P3.2") (pintype "passive"))
    )
    (net (code "321") (name "unconnected-(U$1G-7-PadP3.7)") (class "Default")
      (node (ref "U$1") (pin "P3.7") (pinfunction "7_P3.7") (pintype "passive"))
    )
    (net (code "322") (name "unconnected-(U$1H-2-PadP4.2)") (class "Default")
      (node (ref "U$1") (pin "P4.2") (pinfunction "2_P4.2") (pintype "passive"))
    )
    (net (code "323") (name "unconnected-(U$1H-7-PadP4.7)") (class "Default")
      (node (ref "U$1") (pin "P4.7") (pinfunction "7_P4.7") (pintype "passive"))
    )
    (net (code "324") (name "unconnected-(U$1I-2-PadP5.2)") (class "Default")
      (node (ref "U$1") (pin "P5.2") (pinfunction "2_P5.2") (pintype "passive"))
    )
    (net (code "325") (name "unconnected-(U$1I-7-PadP5.7)") (class "Default")
      (node (ref "U$1") (pin "P5.7") (pinfunction "7_P5.7") (pintype "passive"))
    )
    (net (code "326") (name "unconnected-(U$1J-2-PadP6.2)") (class "Default")
      (node (ref "U$1") (pin "P6.2") (pinfunction "2_P6.2") (pintype "passive"))
    )
    (net (code "327") (name "unconnected-(U$1J-7-PadP6.7)") (class "Default")
      (node (ref "U$1") (pin "P6.7") (pinfunction "7_P6.7") (pintype "passive"))
    )
    (net (code "328") (name "unconnected-(U$1K-2-PadP7.2)") (class "Default")
      (node (ref "U$1") (pin "P7.2") (pinfunction "2_P7.2") (pintype "passive"))
    )
    (net (code "329") (name "unconnected-(U$1K-7-PadP7.7)") (class "Default")
      (node (ref "U$1") (pin "P7.7") (pinfunction "7_P7.7") (pintype "passive"))
    )
    (net (code "330") (name "unconnected-(U$1L-2-PadP8.2)") (class "Default")
      (node (ref "U$1") (pin "P8.2") (pinfunction "2_P8.2") (pintype "passive"))
    )
    (net (code "331") (name "unconnected-(U$1L-7-PadP8.7)") (class "Default")
      (node (ref "U$1") (pin "P8.7") (pinfunction "7_P8.7") (pintype "passive"))
    )
    (net (code "332") (name "unconnected-(U$1M-2-PadP9.2)") (class "Default")
      (node (ref "U$1") (pin "P9.2") (pinfunction "2_P9.2") (pintype "passive"))
    )
    (net (code "333") (name "unconnected-(U$1M-7-PadP9.7)") (class "Default")
      (node (ref "U$1") (pin "P9.7") (pinfunction "7_P9.7") (pintype "passive"))
    )
    (net (code "334") (name "unconnected-(USB_HOST-PadID)") (class "Default")
      (node (ref "USB_HOST") (pin "ID") (pinfunction "ID_ID") (pintype "bidirectional"))
    )
    (net (code "335") (name "unconnected-(USB_HOST-PadPAD1)") (class "Default")
      (node (ref "USB_HOST") (pin "PAD1") (pinfunction "PAD1_PAD1") (pintype "bidirectional"))
    )
    (net (code "336") (name "unconnected-(USB_HOST-PadPAD2)") (class "Default")
      (node (ref "USB_HOST") (pin "PAD2") (pinfunction "PAD2_PAD2") (pintype "bidirectional"))
    )
    (net (code "337") (name "unconnected-(USB_HOST-PadPAD3)") (class "Default")
      (node (ref "USB_HOST") (pin "PAD3") (pinfunction "PAD3_PAD3") (pintype "bidirectional"))
    )
    (net (code "338") (name "unconnected-(USB_HOST-PadPAD4)") (class "Default")
      (node (ref "USB_HOST") (pin "PAD4") (pinfunction "PAD4_PAD4") (pintype "bidirectional"))
    )
    (net (code "339") (name "unconnected-(USB_HOST-PadPAD5)") (class "Default")
      (node (ref "USB_HOST") (pin "PAD5") (pinfunction "PAD5_PAD5") (pintype "bidirectional"))
    )
    (net (code "340") (name "unconnected-(USB_HOST-PadPAD6)") (class "Default")
      (node (ref "USB_HOST") (pin "PAD6") (pinfunction "PAD6_PAD6") (pintype "bidirectional"))
    )
    (net (code "341") (name "unconnected-(USB_HOST-PadV)") (class "Default")
      (node (ref "USB_HOST") (pin "V") (pinfunction "V_V") (pintype "bidirectional"))
    )
    (net (code "342") (name "unconnected-(X1-1-Pad8)") (class "Default")
      (node (ref "X1") (pin "8") (pinfunction "1_8") (pintype "passive"))
    )
    (net (code "343") (name "unconnected-(X1-2-Pad7)") (class "Default")
      (node (ref "X1") (pin "7") (pinfunction "2_7") (pintype "passive"))
    )
    (net (code "344") (name "unconnected-(X1-4-Pad5)") (class "Default")
      (node (ref "X1") (pin "5") (pinfunction "4_5") (pintype "passive"))
    )
    (net (code "345") (name "unconnected-(X1-5-Pad4)") (class "Default")
      (node (ref "X1") (pin "4") (pinfunction "5_4") (pintype "passive"))
    )
    (net (code "346") (name "~{RESET}") (class "Default")
      (node (ref "C37") (pin "2") (pinfunction "2_2") (pintype "passive"))
      (node (ref "FTDI1") (pin "14") (pinfunction "RESET#_14") (pintype "input"))
      (node (ref "FTDI2") (pin "14") (pinfunction "RESET#_14") (pintype "input"))
      (node (ref "FTDI3") (pin "14") (pinfunction "RESET#_14") (pintype "input"))
      (node (ref "HUB") (pin "4") (pinfunction "~{RESET}_4") (pintype "input"))
      (node (ref "R7") (pin "1") (pinfunction "1_1") (pintype "passive"))
    )
  )
)
